# Sheet1.net
KiCad netlist of a schematic drawn in Altium Designer
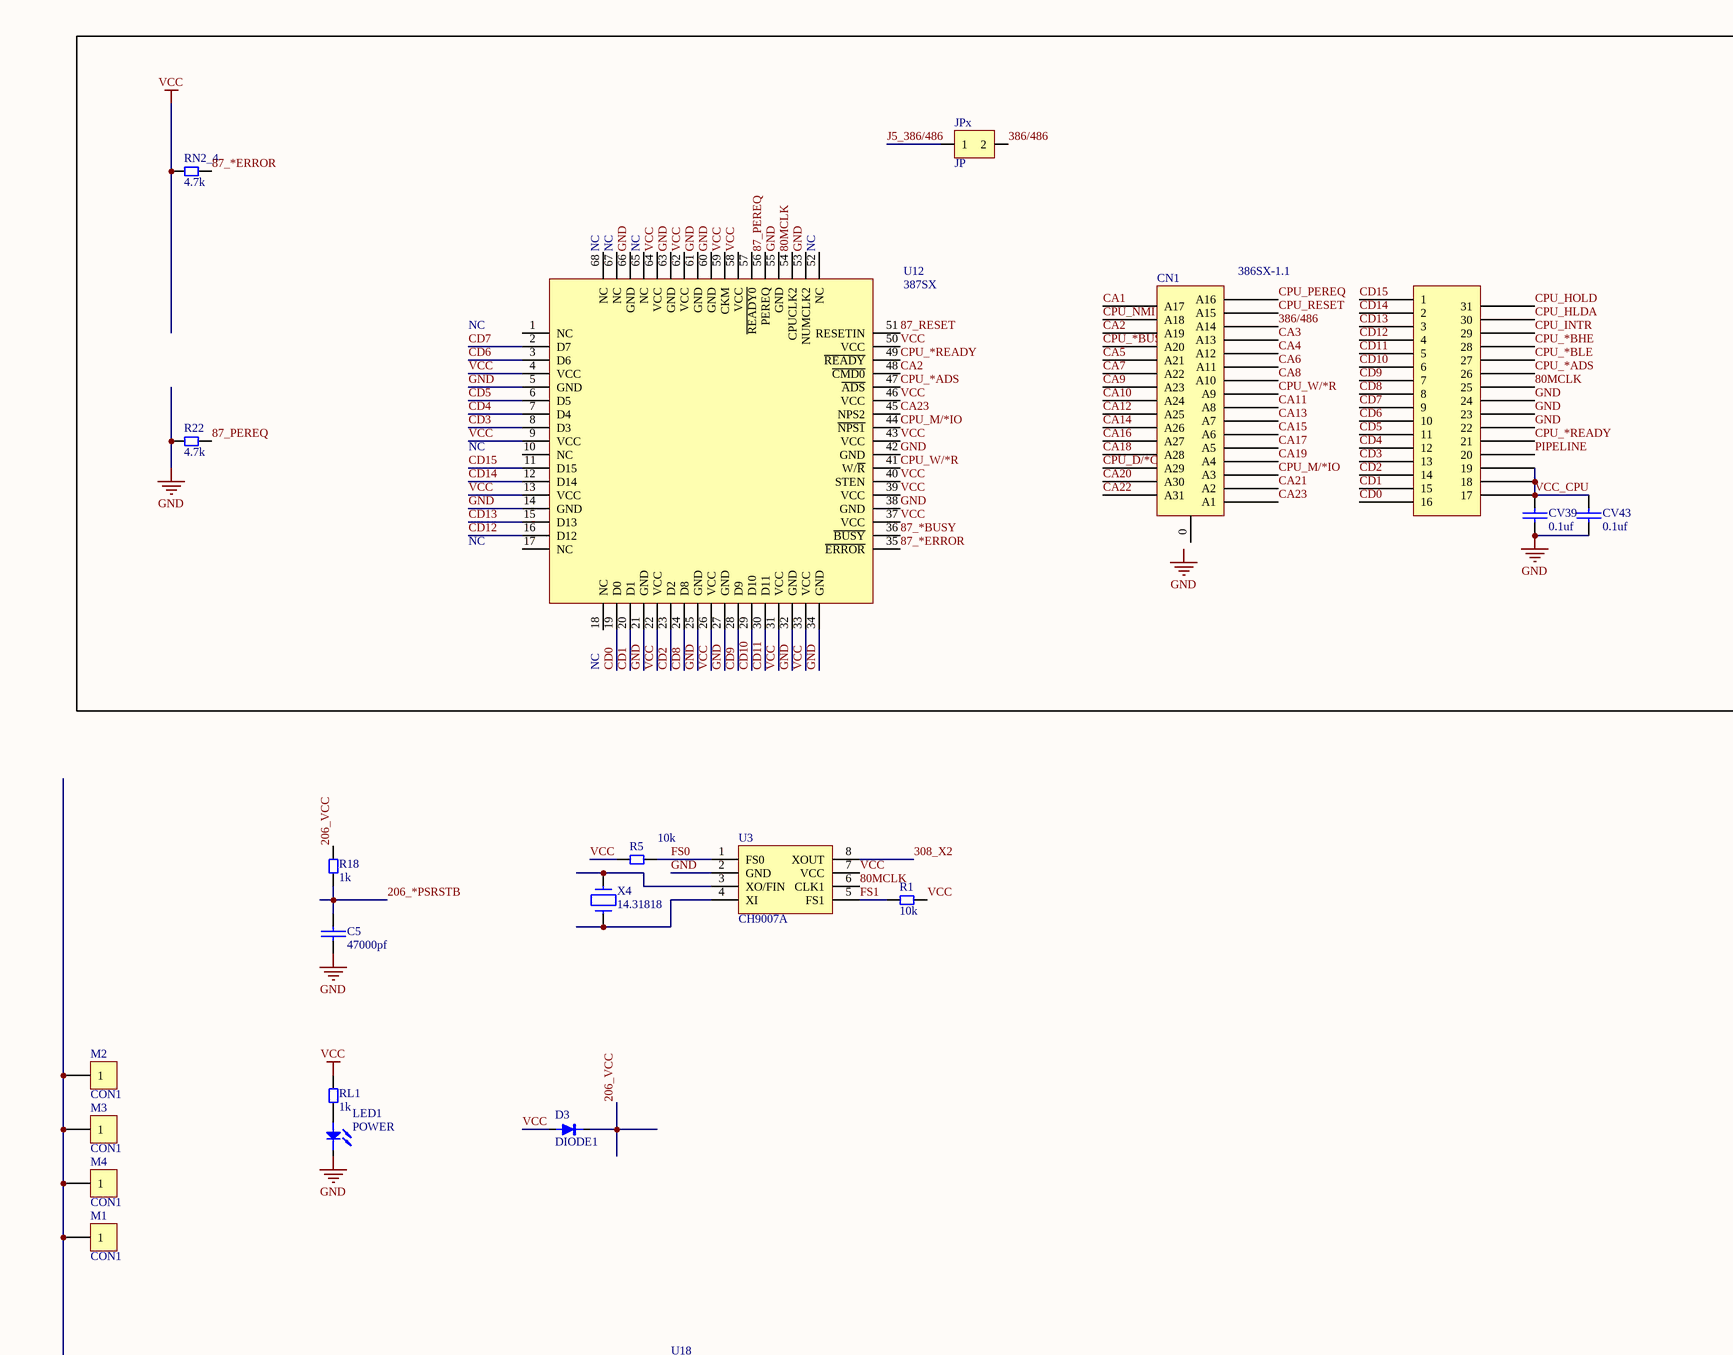
[diagram p0: Sheet1.SchDoc, top left]
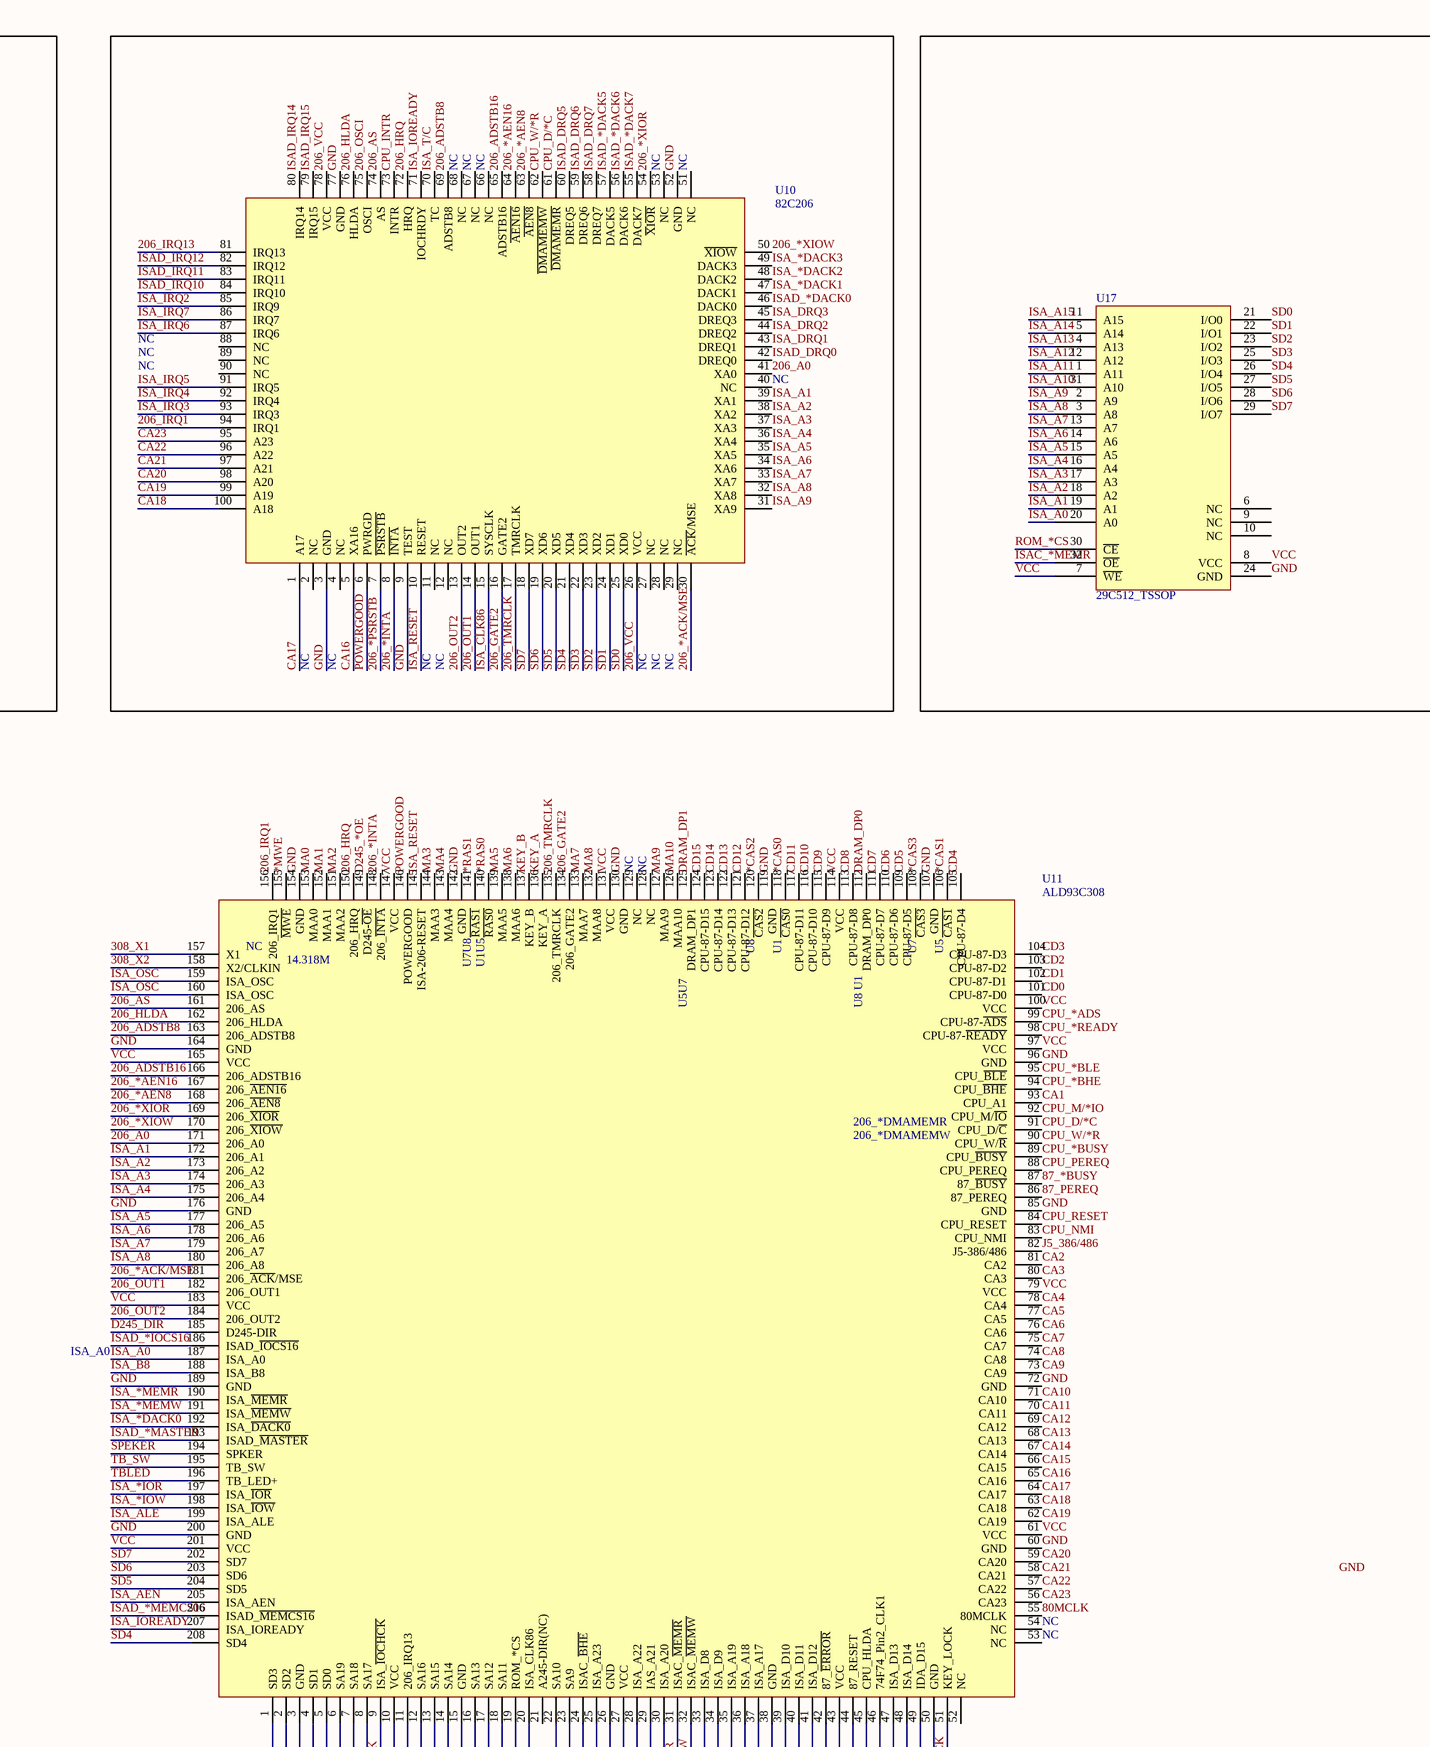
[diagram p1: Sheet1.SchDoc, top middle]
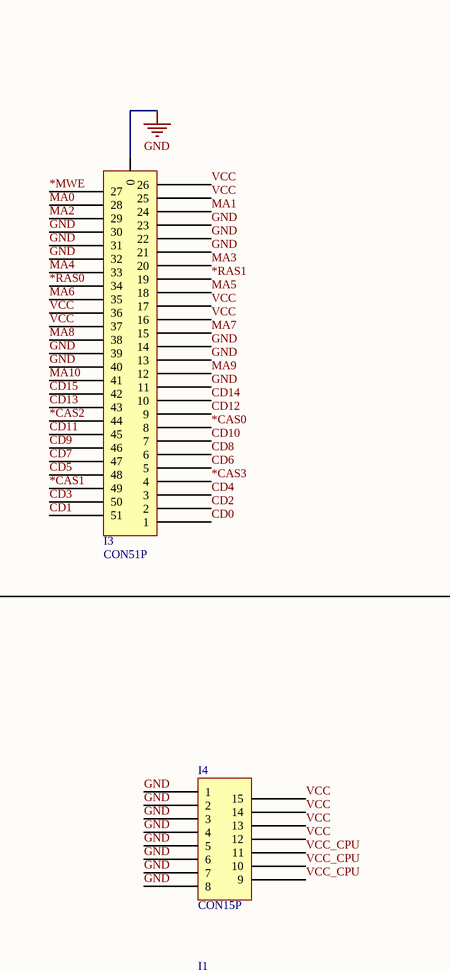
[diagram p2: Sheet1.SchDoc, top right]
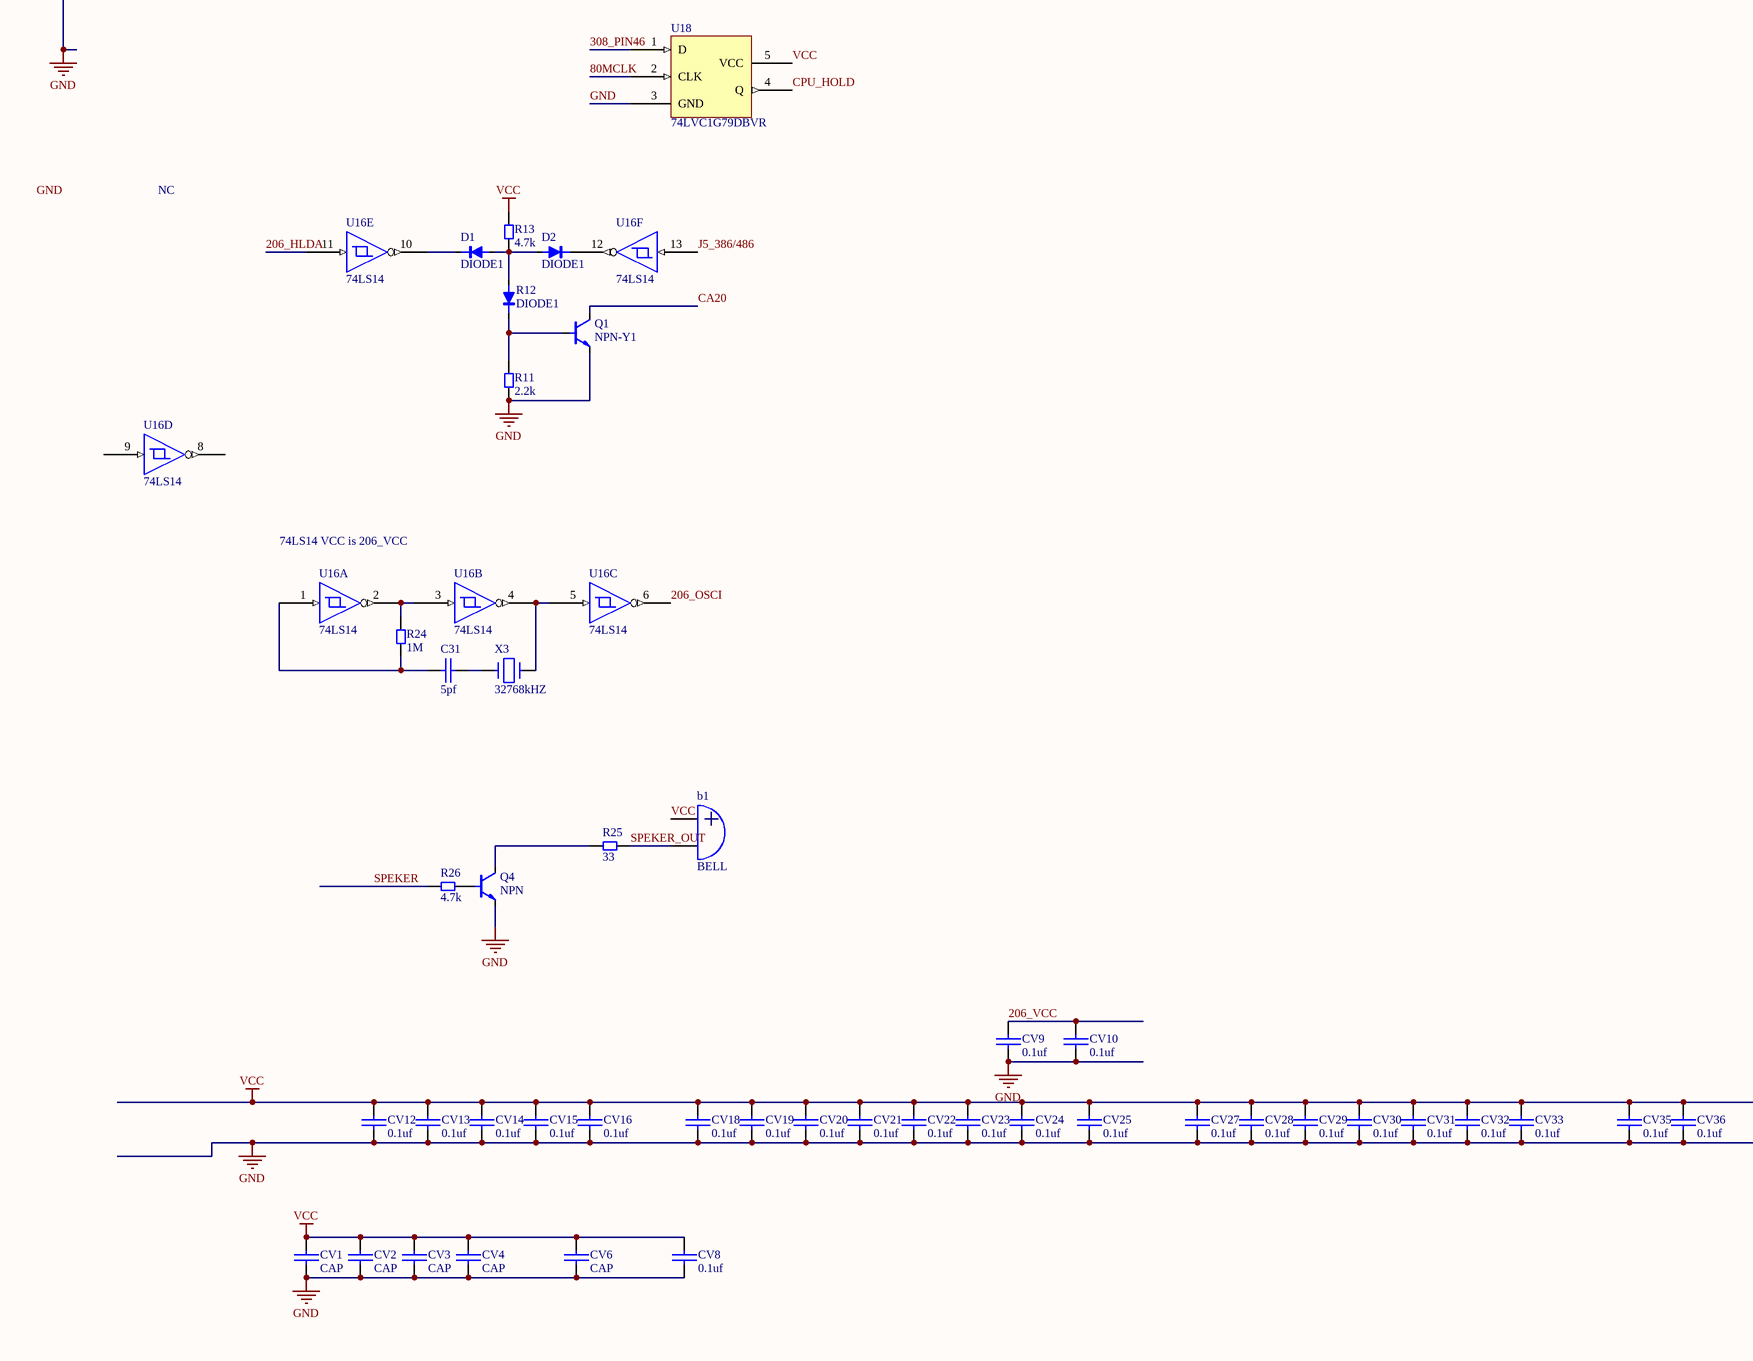
[diagram p3: Sheet1.SchDoc, bottom left]
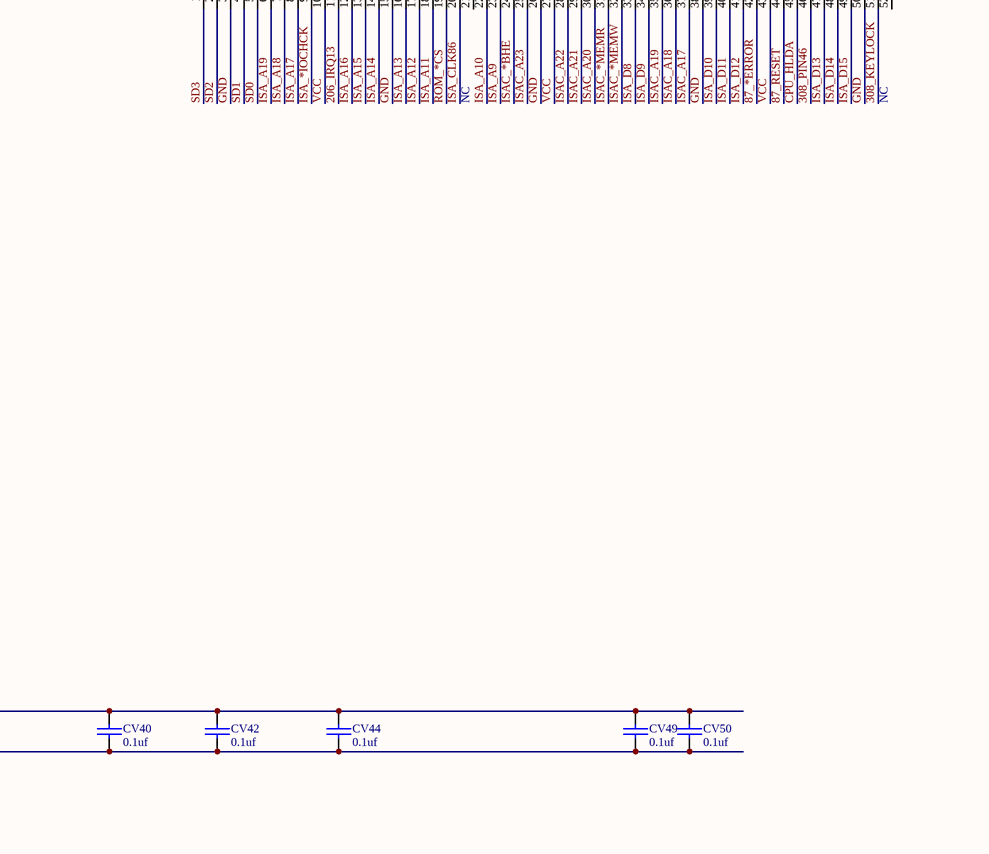
[diagram p4: Sheet1.SchDoc, bottom middle]
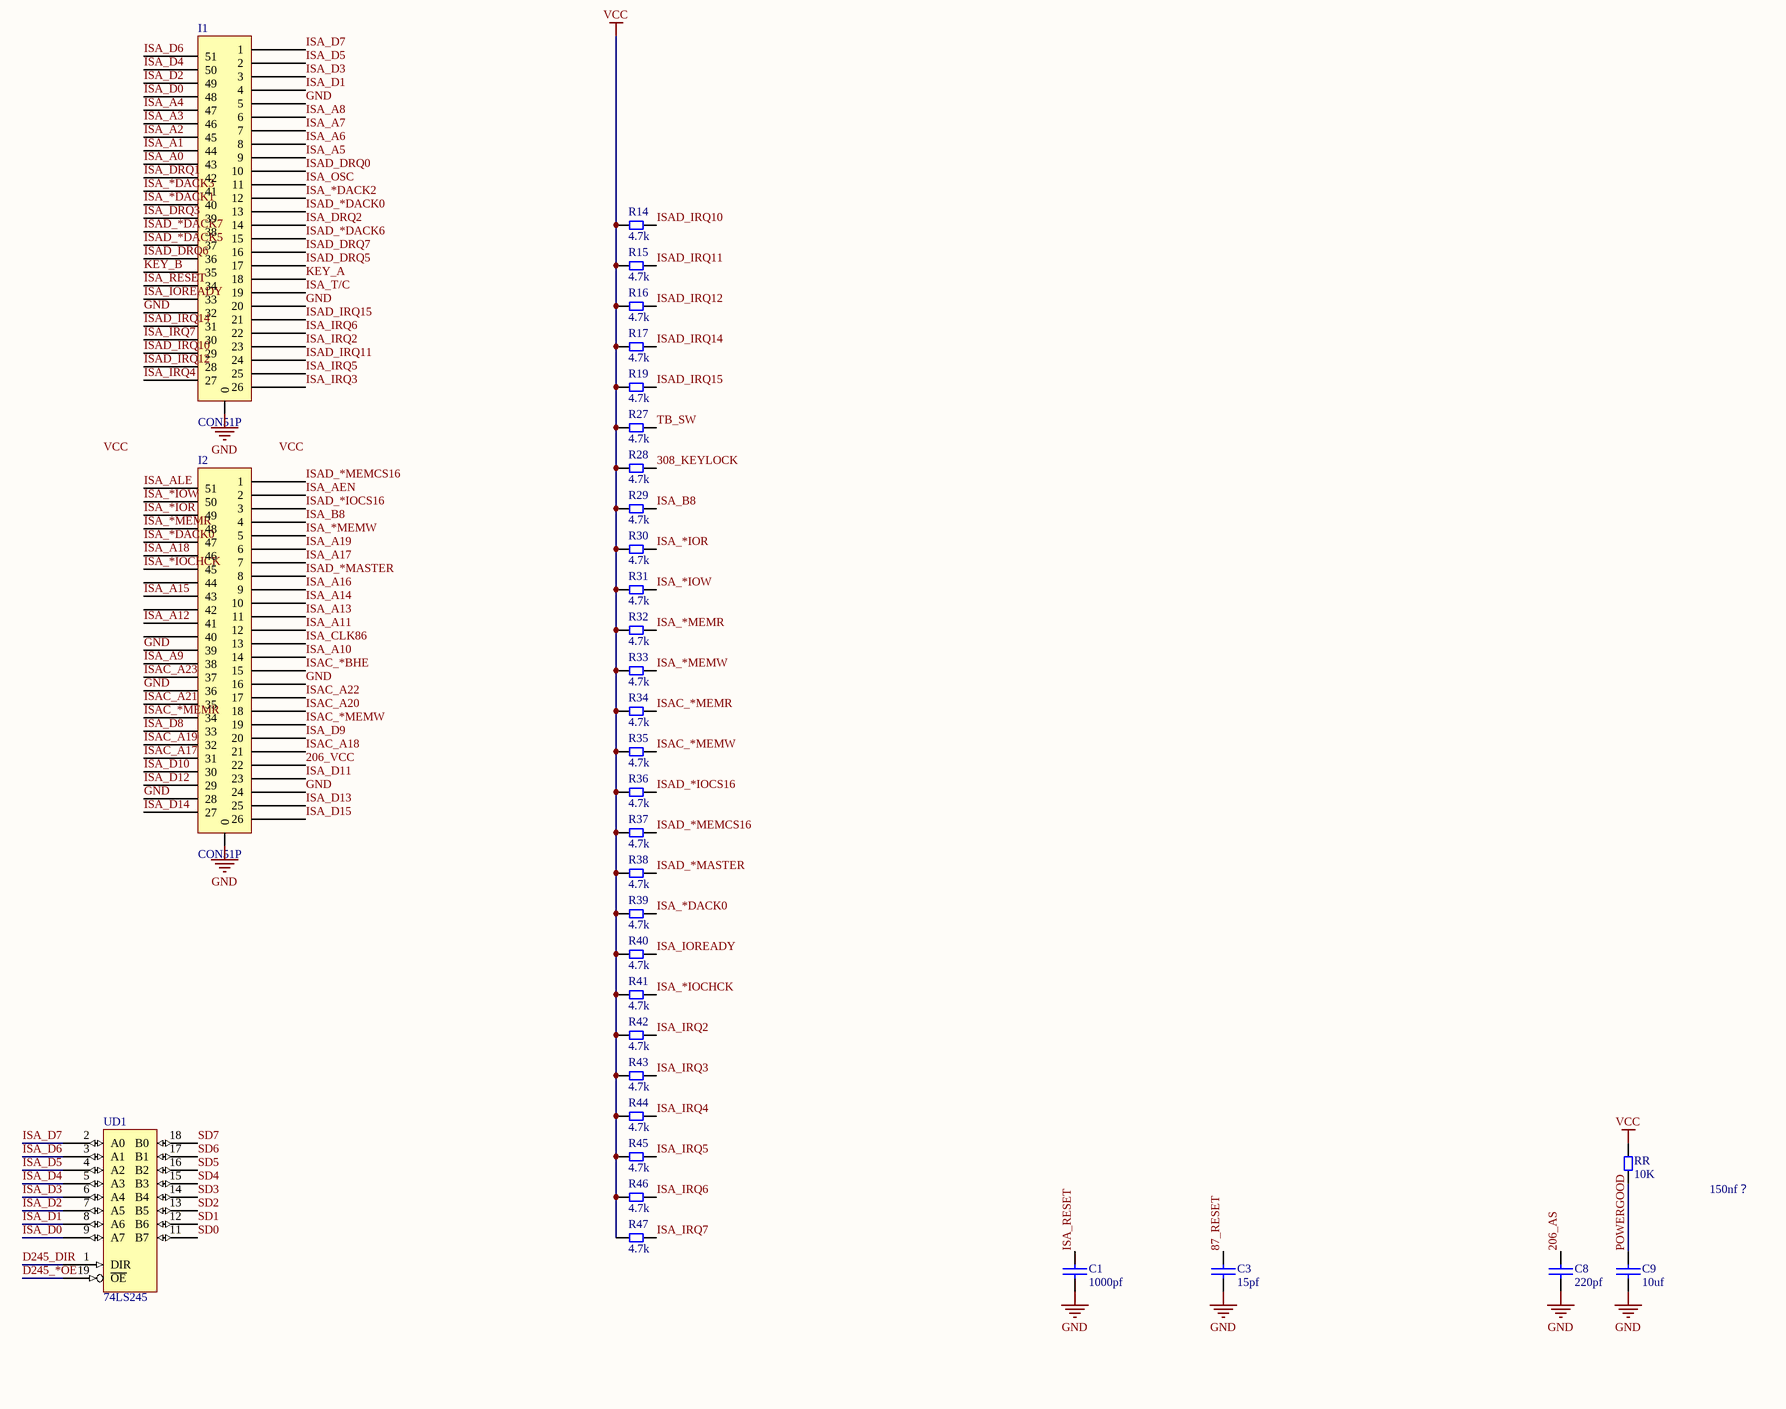
[diagram p5: Sheet1.SchDoc, bottom right]

(export (version "E")
  (design (tool "Eeschema 10.0.6"))
  (components
    (comp (ref "b1") (value "BELL") (footprint "BELL_8530") (libsource (lib "常用元件库") (part "BELL")))
    (comp (ref "C1") (value "1000pf") (footprint "C0603") (libsource (lib "电阻电容二极管") (part "CAP")))
    (comp (ref "C3") (value "15pf") (footprint "C0603") (libsource (lib "电阻电容二极管") (part "CAP")))
    (comp (ref "C5") (value "47000pf") (footprint "C0603") (libsource (lib "电阻电容二极管") (part "CAP")))
    (comp (ref "C8") (value "220pf") (footprint "C0603") (libsource (lib "电阻电容二极管") (part "CAP")))
    (comp (ref "C9") (value "10uf") (footprint "C0603") (libsource (lib "电阻电容二极管") (part "CAP")))
    (comp (ref "C31") (value "5pf") (footprint "C0603") (libsource (lib "电阻电容二极管") (part "CAP")))
    (comp (ref "CN1") (value "386SX-1.1") (footprint "MY-386SX1") (libsource (lib "微机原理") (part "386SX-1.1")))
    (comp (ref "CV1") (value "CAP") (footprint "C0805") (libsource (lib "电阻电容二极管") (part "CAP")))
    (comp (ref "CV2") (value "CAP") (footprint "C0805") (libsource (lib "电阻电容二极管") (part "CAP")))
    (comp (ref "CV3") (value "CAP") (footprint "C0805") (libsource (lib "电阻电容二极管") (part "CAP")))
    (comp (ref "CV4") (value "CAP") (footprint "C0805") (libsource (lib "电阻电容二极管") (part "CAP")))
    (comp (ref "CV6") (value "CAP") (footprint "C0805") (libsource (lib "电阻电容二极管") (part "CAP")))
    (comp (ref "CV8") (value "0.1uf") (footprint "C0603") (libsource (lib "电阻电容二极管") (part "CAP")))
    (comp (ref "CV9") (value "0.1uf") (footprint "C0603") (libsource (lib "电阻电容二极管") (part "CAP")))
    (comp (ref "CV10") (value "0.1uf") (footprint "C0603") (libsource (lib "电阻电容二极管") (part "CAP")))
    (comp (ref "CV12") (value "0.1uf") (footprint "C0603") (libsource (lib "电阻电容二极管") (part "CAP")))
    (comp (ref "CV13") (value "0.1uf") (footprint "C0603") (libsource (lib "电阻电容二极管") (part "CAP")))
    (comp (ref "CV14") (value "0.1uf") (footprint "C0603") (libsource (lib "电阻电容二极管") (part "CAP")))
    (comp (ref "CV15") (value "0.1uf") (footprint "C0603") (libsource (lib "电阻电容二极管") (part "CAP")))
    (comp (ref "CV16") (value "0.1uf") (footprint "C0603") (libsource (lib "电阻电容二极管") (part "CAP")))
    (comp (ref "CV18") (value "0.1uf") (footprint "C0603") (libsource (lib "电阻电容二极管") (part "CAP")))
    (comp (ref "CV19") (value "0.1uf") (footprint "C0603") (libsource (lib "电阻电容二极管") (part "CAP")))
    (comp (ref "CV20") (value "0.1uf") (footprint "C0603") (libsource (lib "电阻电容二极管") (part "CAP")))
    (comp (ref "CV21") (value "0.1uf") (footprint "C0603") (libsource (lib "电阻电容二极管") (part "CAP")))
    (comp (ref "CV22") (value "0.1uf") (footprint "C0603") (libsource (lib "电阻电容二极管") (part "CAP")))
    (comp (ref "CV23") (value "0.1uf") (footprint "C0603") (libsource (lib "电阻电容二极管") (part "CAP")))
    (comp (ref "CV24") (value "0.1uf") (footprint "C0603") (libsource (lib "电阻电容二极管") (part "CAP")))
    (comp (ref "CV25") (value "0.1uf") (footprint "C0603") (libsource (lib "电阻电容二极管") (part "CAP")))
    (comp (ref "CV27") (value "0.1uf") (footprint "C0603") (libsource (lib "电阻电容二极管") (part "CAP")))
    (comp (ref "CV28") (value "0.1uf") (footprint "C0603") (libsource (lib "电阻电容二极管") (part "CAP")))
    (comp (ref "CV29") (value "0.1uf") (footprint "C0603") (libsource (lib "电阻电容二极管") (part "CAP")))
    (comp (ref "CV30") (value "0.1uf") (footprint "C0603") (libsource (lib "电阻电容二极管") (part "CAP")))
    (comp (ref "CV31") (value "0.1uf") (footprint "C0603") (libsource (lib "电阻电容二极管") (part "CAP")))
    (comp (ref "CV32") (value "0.1uf") (footprint "C0603") (libsource (lib "电阻电容二极管") (part "CAP")))
    (comp (ref "CV33") (value "0.1uf") (footprint "C0603") (libsource (lib "电阻电容二极管") (part "CAP")))
    (comp (ref "CV35") (value "0.1uf") (footprint "C0603") (libsource (lib "电阻电容二极管") (part "CAP")))
    (comp (ref "CV36") (value "0.1uf") (footprint "C0603") (libsource (lib "电阻电容二极管") (part "CAP")))
    (comp (ref "CV39") (value "0.1uf") (footprint "C0603") (libsource (lib "电阻电容二极管") (part "CAP")))
    (comp (ref "CV40") (value "0.1uf") (footprint "C0603") (libsource (lib "电阻电容二极管") (part "CAP")))
    (comp (ref "CV42") (value "0.1uf") (footprint "C0603") (libsource (lib "电阻电容二极管") (part "CAP")))
    (comp (ref "CV43") (value "0.1uf") (footprint "C0603") (libsource (lib "电阻电容二极管") (part "CAP")))
    (comp (ref "CV44") (value "0.1uf") (footprint "C0603") (libsource (lib "电阻电容二极管") (part "CAP")))
    (comp (ref "CV49") (value "0.1uf") (footprint "C0603") (libsource (lib "电阻电容二极管") (part "CAP")))
    (comp (ref "CV50") (value "0.1uf") (footprint "C0603") (libsource (lib "电阻电容二极管") (part "CAP")))
    (comp (ref "D1") (value "DIODE1") (footprint "SOD323") (libsource (lib "电阻电容二极管") (part "DIODE1")))
    (comp (ref "D2") (value "DIODE1") (footprint "SOD323") (libsource (lib "电阻电容二极管") (part "DIODE1")))
    (comp (ref "D3") (value "DIODE1") (footprint "SMx") (libsource (lib "常用元件库") (part "DIODE1")))
    (comp (ref "I1") (value "CON51P") (footprint "BTB1.0-51P-b") (libsource (lib "常用元件库") (part "CON51P")))
    (comp (ref "I2") (value "CON51P") (footprint "BTB1.0-51P-b") (libsource (lib "常用元件库") (part "CON51P")))
    (comp (ref "I3") (value "CON51P") (footprint "BTB1.0-51P-b") (libsource (lib "") (part "CON51P_1")))
    (comp (ref "I4") (value "CON15P") (footprint "BTB1.0-15P-B") (libsource (lib "常用元件库") (part "CON15P")))
    (comp (ref "JPx") (value "JP") (footprint "SIP2(2.0)") (libsource (lib "常用元件库") (part "JP-2")))
    (comp (ref "LED1") (value "POWER") (footprint "LED0603") (libsource (lib "电阻电容二极管") (part "LED")))
    (comp (ref "M1") (value "CON1") (footprint "M2A") (libsource (lib "常用元件库") (part "CON1")))
    (comp (ref "M2") (value "CON1") (footprint "MY-M2") (libsource (lib "常用元件库") (part "CON1")))
    (comp (ref "M3") (value "CON1") (footprint "MY-M2") (libsource (lib "常用元件库") (part "CON1")))
    (comp (ref "M4") (value "CON1") (footprint "M2A") (libsource (lib "常用元件库") (part "CON1")))
    (comp (ref "Q1") (value "NPN-Y1") (footprint "SOT23") (libsource (lib "电阻电容二极管") (part "NPN")))
    (comp (ref "Q4") (value "NPN") (footprint "SOT23") (libsource (lib "电阻电容二极管") (part "NPN")))
    (comp (ref "R1") (value "10k") (footprint "R0603") (libsource (lib "电阻电容二极管") (part "RES2")))
    (comp (ref "R5") (value "10k") (footprint "R0603") (libsource (lib "电阻电容二极管") (part "RES2")))
    (comp (ref "R11") (value "2.2k") (footprint "R0603") (libsource (lib "电阻电容二极管") (part "RES2")))
    (comp (ref "R12") (value "DIODE1") (footprint "SOD323") (libsource (lib "电阻电容二极管") (part "DIODE1")))
    (comp (ref "R13") (value "4.7k") (footprint "R0603") (libsource (lib "电阻电容二极管") (part "RES2")))
    (comp (ref "R14") (value "4.7k") (footprint "R0603") (libsource (lib "电阻电容二极管") (part "RES2")))
    (comp (ref "R15") (value "4.7k") (footprint "R0603") (libsource (lib "电阻电容二极管") (part "RES2")))
    (comp (ref "R16") (value "4.7k") (footprint "R0603") (libsource (lib "电阻电容二极管") (part "RES2")))
    (comp (ref "R17") (value "4.7k") (footprint "R0603") (libsource (lib "电阻电容二极管") (part "RES2")))
    (comp (ref "R18") (value "1k") (footprint "R0603") (libsource (lib "电阻电容二极管") (part "RES2")))
    (comp (ref "R19") (value "4.7k") (footprint "R0603") (libsource (lib "电阻电容二极管") (part "RES2")))
    (comp (ref "R22") (value "4.7k") (footprint "R0603") (libsource (lib "电阻电容二极管") (part "RES2")))
    (comp (ref "R24") (value "1M") (footprint "R0603") (libsource (lib "电阻电容二极管") (part "RES2")))
    (comp (ref "R25") (value "33") (footprint "R0603") (libsource (lib "电阻电容二极管") (part "RES2")))
    (comp (ref "R26") (value "4.7k") (footprint "R0603") (libsource (lib "电阻电容二极管") (part "RES2")))
    (comp (ref "R27") (value "4.7k") (footprint "R0603") (libsource (lib "电阻电容二极管") (part "RES2")))
    (comp (ref "R28") (value "4.7k") (footprint "R0603") (libsource (lib "电阻电容二极管") (part "RES2")))
    (comp (ref "R29") (value "4.7k") (footprint "R0603") (libsource (lib "电阻电容二极管") (part "RES2")))
    (comp (ref "R30") (value "4.7k") (footprint "R0603") (libsource (lib "电阻电容二极管") (part "RES2")))
    (comp (ref "R31") (value "4.7k") (footprint "R0603") (libsource (lib "电阻电容二极管") (part "RES2")))
    (comp (ref "R32") (value "4.7k") (footprint "R0603") (libsource (lib "电阻电容二极管") (part "RES2")))
    (comp (ref "R33") (value "4.7k") (footprint "R0603") (libsource (lib "电阻电容二极管") (part "RES2")))
    (comp (ref "R34") (value "4.7k") (footprint "R0603") (libsource (lib "电阻电容二极管") (part "RES2")))
    (comp (ref "R35") (value "4.7k") (footprint "R0603") (libsource (lib "电阻电容二极管") (part "RES2")))
    (comp (ref "R36") (value "4.7k") (footprint "R0603") (libsource (lib "电阻电容二极管") (part "RES2")))
    (comp (ref "R37") (value "4.7k") (footprint "R0603") (libsource (lib "电阻电容二极管") (part "RES2")))
    (comp (ref "R38") (value "4.7k") (footprint "R0603") (libsource (lib "电阻电容二极管") (part "RES2")))
    (comp (ref "R39") (value "4.7k") (footprint "R0603") (libsource (lib "电阻电容二极管") (part "RES2")))
    (comp (ref "R40") (value "4.7k") (footprint "R0603") (libsource (lib "电阻电容二极管") (part "RES2")))
    (comp (ref "R41") (value "4.7k") (footprint "R0603") (libsource (lib "电阻电容二极管") (part "RES2")))
    (comp (ref "R42") (value "4.7k") (footprint "R0603") (libsource (lib "电阻电容二极管") (part "RES2")))
    (comp (ref "R43") (value "4.7k") (footprint "R0603") (libsource (lib "电阻电容二极管") (part "RES2")))
    (comp (ref "R44") (value "4.7k") (footprint "R0603") (libsource (lib "电阻电容二极管") (part "RES2")))
    (comp (ref "R45") (value "4.7k") (footprint "R0603") (libsource (lib "电阻电容二极管") (part "RES2")))
    (comp (ref "R46") (value "4.7k") (footprint "R0603") (libsource (lib "电阻电容二极管") (part "RES2")))
    (comp (ref "R47") (value "4.7k") (footprint "R0603") (libsource (lib "电阻电容二极管") (part "RES2")))
    (comp (ref "RL1") (value "1k") (footprint "R0603") (libsource (lib "电阻电容二极管") (part "RES2")))
    (comp (ref "RN2_4") (value "4.7k") (footprint "R0603") (libsource (lib "电阻电容二极管") (part "RES2")))
    (comp (ref "RR") (value "10K") (footprint "R0603") (libsource (lib "电阻电容二极管") (part "RES2")))
    (comp (ref "U3") (value "CH9007A") (footprint "DIP8 - SOJ") (libsource (lib "微机原理") (part "CH9007A")))
    (comp (ref "U10") (value "82C206") (footprint "PQFP100B") (libsource (lib "微机原理") (part "82C206")))
    (comp (ref "U11") (value "ALD93C308") (libsource (lib "微机原理") (part "ALD93C308")))
    (comp (ref "U12") (value "387SX") (footprint "PLCC68") (libsource (lib "微机原理") (part "387SX")))
    (comp (ref "U16") (value "74LS14") (footprint "SO-14") (libsource (lib "TTL74系列IC") (part "74LS14")))
    (comp (ref "U17")
      (value "29C512_TSSOP")
      (footprint "TSSOP32")
      (libsource (lib "微机原理") (part "29C512_TSSOP"))
    )
    (comp (ref "U18")
      (value "74LVC1G79DBVR")
      (footprint "SOT23-5")
      (libsource (lib "微机原理") (part "74LVC1G79DBVR"))
    )
    (comp (ref "UD1") (value "74LS245") (footprint "TSSOP-20") (libsource (lib "微机原理") (part "74LS245")))
    (comp (ref "X3") (value "32768kHZ") (footprint "CRY3215A") (libsource (lib "常用元件库") (part "CRYSTAL")))
    (comp (ref "X4") (value "14.31818") (footprint "5032") (libsource (lib "常用元件库") (part "CRYSTAL")))
  )
  (nets
    (net (code "1") (name "/*CAS0") (class "Default")
      (node (ref "I3") (pin "8") (pinfunction "8_8") (pintype "passive"))
      (node (ref "U11") (pin "118") (pinfunction "~{CAS0}_118") (pintype "passive"))
    )
    (net (code "2") (name "/*CAS1") (class "Default")
      (node (ref "I3") (pin "49") (pinfunction "49_49") (pintype "passive"))
      (node (ref "U11") (pin "106") (pinfunction "~{CAS1}_106") (pintype "passive"))
    )
    (net (code "3") (name "/*CAS2") (class "Default")
      (node (ref "I3") (pin "44") (pinfunction "44_44") (pintype "passive"))
      (node (ref "U11") (pin "120") (pinfunction "~{CAS2}_120") (pintype "passive"))
    )
    (net (code "4") (name "/*CAS3") (class "Default")
      (node (ref "I3") (pin "4") (pinfunction "4_4") (pintype "passive"))
      (node (ref "U11") (pin "108") (pinfunction "~{CAS3}_108") (pintype "passive"))
    )
    (net (code "5") (name "/*MWE") (class "Default")
      (node (ref "I3") (pin "27") (pinfunction "27_27") (pintype "passive"))
      (node (ref "U11") (pin "155") (pinfunction "~{MWE}_155") (pintype "passive"))
    )
    (net (code "6") (name "/*RAS0") (class "Default")
      (node (ref "I3") (pin "34") (pinfunction "34_34") (pintype "passive"))
      (node (ref "U11") (pin "140") (pinfunction "~{RAS0}_140") (pintype "passive"))
    )
    (net (code "7") (name "/*RAS1") (class "Default")
      (node (ref "I3") (pin "19") (pinfunction "19_19") (pintype "passive"))
      (node (ref "U11") (pin "141") (pinfunction "~{RAS1}_141") (pintype "passive"))
    )
    (net (code "8") (name "/80MCLK") (class "Default")
      (node (ref "CN1") (pin "25") (pinfunction "25_25") (pintype "passive"))
      (node (ref "U11") (pin "55") (pinfunction "80MCLK_55") (pintype "passive"))
      (node (ref "U12") (pin "54") (pinfunction "CPUCLK2_54") (pintype "passive"))
      (node (ref "U18") (pin "2") (pinfunction "CLK_2") (pintype "input"))
      (node (ref "U3") (pin "6") (pinfunction "CLK1_6") (pintype "passive"))
    )
    (net (code "9") (name "/87_*BUSY") (class "Default")
      (node (ref "U11") (pin "87") (pinfunction "87_~{BUSY}_87") (pintype "passive"))
      (node (ref "U12") (pin "36") (pinfunction "~{BUSY}_36") (pintype "passive"))
    )
    (net (code "10") (name "/87_*ERROR") (class "Default")
      (node (ref "RN2_4") (pin "1") (pinfunction "1_1") (pintype "passive"))
      (node (ref "U11") (pin "42") (pinfunction "87_~{ERROR}_42") (pintype "passive"))
      (node (ref "U12") (pin "35") (pinfunction "~{ERROR}_35") (pintype "passive"))
    )
    (net (code "11") (name "/87_PEREQ") (class "Default")
      (node (ref "R22") (pin "2") (pinfunction "2_2") (pintype "passive"))
      (node (ref "U11") (pin "86") (pinfunction "87_PEREQ_86") (pintype "passive"))
      (node (ref "U12") (pin "56") (pinfunction "PEREQ_56") (pintype "passive"))
    )
    (net (code "12") (name "/87_RESET") (class "Default")
      (node (ref "C3") (pin "1") (pinfunction "1_1") (pintype "passive"))
      (node (ref "U11") (pin "44") (pinfunction "87_RESET_44") (pintype "passive"))
      (node (ref "U12") (pin "51") (pinfunction "RESETIN_51") (pintype "passive"))
    )
    (net (code "13") (name "/206_*ACK{slash}MSE") (class "Default")
      (node (ref "U10") (pin "30") (pinfunction "~{ACK}/MSE_30") (pintype "passive"))
      (node (ref "U11") (pin "181") (pinfunction "206_~{ACK}/MSE_181") (pintype "passive"))
    )
    (net (code "14") (name "/206_*AEN8") (class "Default")
      (node (ref "U10") (pin "63") (pinfunction "~{AEN8}_63") (pintype "passive"))
      (node (ref "U11") (pin "168") (pinfunction "206_~{AEN8}_168") (pintype "passive"))
    )
    (net (code "15") (name "/206_*AEN16") (class "Default")
      (node (ref "U10") (pin "64") (pinfunction "~{AEN16}_64") (pintype "passive"))
      (node (ref "U11") (pin "167") (pinfunction "206_~{AEN16}_167") (pintype "passive"))
    )
    (net (code "16") (name "/206_*INTA") (class "Default")
      (node (ref "U10") (pin "8") (pinfunction "~{INTA}_8") (pintype "passive"))
      (node (ref "U11") (pin "148") (pinfunction "206_~{INTA}_148") (pintype "passive"))
    )
    (net (code "17") (name "/206_*PSRSTB") (class "Default")
      (node (ref "C5") (pin "2") (pinfunction "2_2") (pintype "passive"))
      (node (ref "R18") (pin "1") (pinfunction "1_1") (pintype "passive"))
      (node (ref "U10") (pin "7") (pinfunction "~{PSRSTB}_7") (pintype "passive"))
    )
    (net (code "18") (name "/206_*XIOR") (class "Default")
      (node (ref "U10") (pin "54") (pinfunction "~{X}I~{OR}_54") (pintype "passive"))
      (node (ref "U11") (pin "169") (pinfunction "206_~{XIOR}_169") (pintype "passive"))
    )
    (net (code "19") (name "/206_*XIOW") (class "Default")
      (node (ref "U10") (pin "50") (pinfunction "~{XIOW}_50") (pintype "passive"))
      (node (ref "U11") (pin "170") (pinfunction "206_~{XIOW}_170") (pintype "passive"))
    )
    (net (code "20") (name "/206_A0") (class "Default")
      (node (ref "U10") (pin "41") (pinfunction "XA0_41") (pintype "passive"))
      (node (ref "U11") (pin "171") (pinfunction "206_A0_171") (pintype "passive"))
    )
    (net (code "21") (name "/206_ADSTB8") (class "Default")
      (node (ref "U10") (pin "69") (pinfunction "ADSTB8_69") (pintype "passive"))
      (node (ref "U11") (pin "163") (pinfunction "206_ADSTB8_163") (pintype "passive"))
    )
    (net (code "22") (name "/206_ADSTB16") (class "Default")
      (node (ref "U10") (pin "65") (pinfunction "ADSTB16_65") (pintype "passive"))
      (node (ref "U11") (pin "166") (pinfunction "206_ADSTB16_166") (pintype "passive"))
    )
    (net (code "23") (name "/206_AS") (class "Default")
      (node (ref "C8") (pin "1") (pinfunction "1_1") (pintype "passive"))
      (node (ref "U10") (pin "74") (pinfunction "AS_74") (pintype "passive"))
      (node (ref "U11") (pin "161") (pinfunction "206_AS_161") (pintype "passive"))
    )
    (net (code "24") (name "/206_GATE2") (class "Default")
      (node (ref "U10") (pin "16") (pinfunction "GATE2_16") (pintype "passive"))
      (node (ref "U11") (pin "134") (pinfunction "206_GATE2_134") (pintype "passive"))
    )
    (net (code "25") (name "/206_HLDA") (class "Default")
      (node (ref "U10") (pin "76") (pinfunction "HLDA_76") (pintype "passive"))
      (node (ref "U11") (pin "162") (pinfunction "206_HLDA_162") (pintype "passive"))
      (node (ref "U16") (pin "11") (pintype "input"))
    )
    (net (code "26") (name "/206_HRQ") (class "Default")
      (node (ref "U10") (pin "72") (pinfunction "HRQ_72") (pintype "passive"))
      (node (ref "U11") (pin "150") (pinfunction "206_HRQ_150") (pintype "passive"))
    )
    (net (code "27") (name "/206_IRQ1") (class "Default")
      (node (ref "U10") (pin "94") (pinfunction "IRQ1_94") (pintype "passive"))
      (node (ref "U11") (pin "156") (pinfunction "206_IRQ1_156") (pintype "passive"))
    )
    (net (code "28") (name "/206_IRQ13") (class "Default")
      (node (ref "U10") (pin "81") (pinfunction "IRQ13_81") (pintype "passive"))
      (node (ref "U11") (pin "11") (pinfunction "206_IRQ13_11") (pintype "passive"))
    )
    (net (code "29") (name "/206_OSCI") (class "Default")
      (node (ref "U10") (pin "75") (pinfunction "OSCI_75") (pintype "passive"))
      (node (ref "U16") (pin "6") (pintype "output"))
    )
    (net (code "30") (name "/206_OUT1") (class "Default")
      (node (ref "U10") (pin "14") (pinfunction "OUT1_14") (pintype "passive"))
      (node (ref "U11") (pin "182") (pinfunction "206_OUT1_182") (pintype "passive"))
    )
    (net (code "31") (name "/206_OUT2") (class "Default")
      (node (ref "U10") (pin "13") (pinfunction "OUT2_13") (pintype "passive"))
      (node (ref "U11") (pin "184") (pinfunction "206_OUT2_184") (pintype "passive"))
    )
    (net (code "32") (name "/206_TMRCLK") (class "Default")
      (node (ref "U10") (pin "17") (pinfunction "TMRCLK_17") (pintype "passive"))
      (node (ref "U11") (pin "135") (pinfunction "206_TMRCLK_135") (pintype "passive"))
    )
    (net (code "33") (name "/206_VCC") (class "Default")
      (node (ref "CV10") (pin "1") (pinfunction "1_1") (pintype "passive"))
      (node (ref "CV9") (pin "1") (pinfunction "1_1") (pintype "passive"))
      (node (ref "D3") (pin "K") (pinfunction "K_K") (pintype "passive"))
      (node (ref "I2") (pin "22") (pinfunction "22_22") (pintype "passive"))
      (node (ref "R18") (pin "2") (pinfunction "2_2") (pintype "passive"))
      (node (ref "U10") (pin "26") (pinfunction "VCC_26") (pintype "passive"))
      (node (ref "U10") (pin "78") (pinfunction "VCC_78") (pintype "passive"))
    )
    (net (code "34") (name "/308_KEYLOCK") (class "Default")
      (node (ref "R28") (pin "2") (pinfunction "2_2") (pintype "passive"))
      (node (ref "U11") (pin "51") (pinfunction "KEY_LOCK_51") (pintype "passive"))
    )
    (net (code "35") (name "/308_PIN46") (class "Default")
      (node (ref "U11") (pin "46") (pinfunction "74F74_Pin2_CLK1_46") (pintype "passive"))
      (node (ref "U18") (pin "1") (pinfunction "D_1") (pintype "input"))
    )
    (net (code "36") (name "/308_X1") (class "Default")
      (node (ref "U11") (pin "157") (pinfunction "X1_157") (pintype "passive"))
    )
    (net (code "37") (name "/308_X2") (class "Default")
      (node (ref "U11") (pin "158") (pinfunction "X2/CLKIN_158") (pintype "passive"))
      (node (ref "U3") (pin "8") (pinfunction "XOUT_8") (pintype "passive"))
    )
    (net (code "38") (name "/386{slash}486") (class "Default")
      (node (ref "CN1") (pin "A14") (pinfunction "A14_A14") (pintype "passive"))
      (node (ref "JPx") (pin "2") (pinfunction "2_2") (pintype "passive"))
    )
    (net (code "39") (name "/CA1") (class "Default")
      (node (ref "CN1") (pin "A17") (pinfunction "A17_A17") (pintype "passive"))
      (node (ref "U11") (pin "93") (pinfunction "CPU_A1_93") (pintype "passive"))
    )
    (net (code "40") (name "/CA2") (class "Default")
      (node (ref "CN1") (pin "A19") (pinfunction "A19_A19") (pintype "passive"))
      (node (ref "U11") (pin "81") (pinfunction "CA2_81") (pintype "passive"))
      (node (ref "U12") (pin "48") (pinfunction "~{CMD0}_48") (pintype "passive"))
    )
    (net (code "41") (name "/CA3") (class "Default")
      (node (ref "CN1") (pin "A13") (pinfunction "A13_A13") (pintype "passive"))
      (node (ref "U11") (pin "80") (pinfunction "CA3_80") (pintype "passive"))
    )
    (net (code "42") (name "/CA4") (class "Default")
      (node (ref "CN1") (pin "A12") (pinfunction "A12_A12") (pintype "passive"))
      (node (ref "U11") (pin "78") (pinfunction "CA4_78") (pintype "passive"))
    )
    (net (code "43") (name "/CA5") (class "Default")
      (node (ref "CN1") (pin "A21") (pinfunction "A21_A21") (pintype "passive"))
      (node (ref "U11") (pin "77") (pinfunction "CA5_77") (pintype "passive"))
    )
    (net (code "44") (name "/CA6") (class "Default")
      (node (ref "CN1") (pin "A11") (pinfunction "A11_A11") (pintype "passive"))
      (node (ref "U11") (pin "76") (pinfunction "CA6_76") (pintype "passive"))
    )
    (net (code "45") (name "/CA7") (class "Default")
      (node (ref "CN1") (pin "A22") (pinfunction "A22_A22") (pintype "passive"))
      (node (ref "U11") (pin "75") (pinfunction "CA7_75") (pintype "passive"))
    )
    (net (code "46") (name "/CA8") (class "Default")
      (node (ref "CN1") (pin "A10") (pinfunction "A10_A10") (pintype "passive"))
      (node (ref "U11") (pin "74") (pinfunction "CA8_74") (pintype "passive"))
    )
    (net (code "47") (name "/CA9") (class "Default")
      (node (ref "CN1") (pin "A23") (pinfunction "A23_A23") (pintype "passive"))
      (node (ref "U11") (pin "73") (pinfunction "CA9_73") (pintype "passive"))
    )
    (net (code "48") (name "/CA10") (class "Default")
      (node (ref "CN1") (pin "A24") (pinfunction "A24_A24") (pintype "passive"))
      (node (ref "U11") (pin "71") (pinfunction "CA10_71") (pintype "passive"))
    )
    (net (code "49") (name "/CA11") (class "Default")
      (node (ref "CN1") (pin "A8") (pinfunction "A8_A8") (pintype "passive"))
      (node (ref "U11") (pin "70") (pinfunction "CA11_70") (pintype "passive"))
    )
    (net (code "50") (name "/CA12") (class "Default")
      (node (ref "CN1") (pin "A25") (pinfunction "A25_A25") (pintype "passive"))
      (node (ref "U11") (pin "69") (pinfunction "CA12_69") (pintype "passive"))
    )
    (net (code "51") (name "/CA13") (class "Default")
      (node (ref "CN1") (pin "A7") (pinfunction "A7_A7") (pintype "passive"))
      (node (ref "U11") (pin "68") (pinfunction "CA13_68") (pintype "passive"))
    )
    (net (code "52") (name "/CA14") (class "Default")
      (node (ref "CN1") (pin "A26") (pinfunction "A26_A26") (pintype "passive"))
      (node (ref "U11") (pin "67") (pinfunction "CA14_67") (pintype "passive"))
    )
    (net (code "53") (name "/CA15") (class "Default")
      (node (ref "CN1") (pin "A6") (pinfunction "A6_A6") (pintype "passive"))
      (node (ref "U11") (pin "66") (pinfunction "CA15_66") (pintype "passive"))
    )
    (net (code "54") (name "/CA16") (class "Default")
      (node (ref "CN1") (pin "A27") (pinfunction "A27_A27") (pintype "passive"))
      (node (ref "U10") (pin "5") (pinfunction "XA16_5") (pintype "passive"))
      (node (ref "U11") (pin "65") (pinfunction "CA16_65") (pintype "passive"))
    )
    (net (code "55") (name "/CA17") (class "Default")
      (node (ref "CN1") (pin "A5") (pinfunction "A5_A5") (pintype "passive"))
      (node (ref "U10") (pin "1") (pinfunction "A17_1") (pintype "passive"))
      (node (ref "U11") (pin "64") (pinfunction "CA17_64") (pintype "passive"))
    )
    (net (code "56") (name "/CA18") (class "Default")
      (node (ref "CN1") (pin "A28") (pinfunction "A28_A28") (pintype "passive"))
      (node (ref "U10") (pin "100") (pinfunction "A18_100") (pintype "passive"))
      (node (ref "U11") (pin "63") (pinfunction "CA18_63") (pintype "passive"))
    )
    (net (code "57") (name "/CA19") (class "Default")
      (node (ref "CN1") (pin "A4") (pinfunction "A4_A4") (pintype "passive"))
      (node (ref "U10") (pin "99") (pinfunction "A19_99") (pintype "passive"))
      (node (ref "U11") (pin "62") (pinfunction "CA19_62") (pintype "passive"))
    )
    (net (code "58") (name "/CA20") (class "Default")
      (node (ref "CN1") (pin "A30") (pinfunction "A30_A30") (pintype "passive"))
      (node (ref "Q1") (pin "C") (pinfunction "c_C") (pintype "passive"))
      (node (ref "U10") (pin "98") (pinfunction "A20_98") (pintype "passive"))
      (node (ref "U11") (pin "59") (pinfunction "CA20_59") (pintype "passive"))
    )
    (net (code "59") (name "/CA21") (class "Default")
      (node (ref "CN1") (pin "A2") (pinfunction "A2_A2") (pintype "passive"))
      (node (ref "U10") (pin "97") (pinfunction "A21_97") (pintype "passive"))
      (node (ref "U11") (pin "58") (pinfunction "CA21_58") (pintype "passive"))
    )
    (net (code "60") (name "/CA22") (class "Default")
      (node (ref "CN1") (pin "A31") (pinfunction "A31_A31") (pintype "passive"))
      (node (ref "U10") (pin "96") (pinfunction "A22_96") (pintype "passive"))
      (node (ref "U11") (pin "57") (pinfunction "CA22_57") (pintype "passive"))
    )
    (net (code "61") (name "/CA23") (class "Default")
      (node (ref "CN1") (pin "A1") (pinfunction "A1_A1") (pintype "passive"))
      (node (ref "U10") (pin "95") (pinfunction "A23_95") (pintype "passive"))
      (node (ref "U11") (pin "56") (pinfunction "CA23_56") (pintype "passive"))
      (node (ref "U12") (pin "45") (pinfunction "NPS2_45") (pintype "passive"))
    )
    (net (code "62") (name "/CD0") (class "Default")
      (node (ref "CN1") (pin "16") (pinfunction "16_16") (pintype "passive"))
      (node (ref "I3") (pin "1") (pinfunction "1_1") (pintype "passive"))
      (node (ref "U11") (pin "101") (pinfunction "CPU-87-D0_101") (pintype "passive"))
      (node (ref "U12") (pin "19") (pinfunction "D0_19") (pintype "passive"))
    )
    (net (code "63") (name "/CD1") (class "Default")
      (node (ref "CN1") (pin "15") (pinfunction "15_15") (pintype "passive"))
      (node (ref "I3") (pin "51") (pinfunction "51_51") (pintype "passive"))
      (node (ref "U11") (pin "102") (pinfunction "CPU-87-D1_102") (pintype "passive"))
      (node (ref "U12") (pin "20") (pinfunction "D1_20") (pintype "passive"))
    )
    (net (code "64") (name "/CD2") (class "Default")
      (node (ref "CN1") (pin "14") (pinfunction "14_14") (pintype "passive"))
      (node (ref "I3") (pin "2") (pinfunction "2_2") (pintype "passive"))
      (node (ref "U11") (pin "103") (pinfunction "CPU-87-D2_103") (pintype "passive"))
      (node (ref "U12") (pin "23") (pinfunction "D2_23") (pintype "passive"))
    )
    (net (code "65") (name "/CD3") (class "Default")
      (node (ref "CN1") (pin "13") (pinfunction "13_13") (pintype "passive"))
      (node (ref "I3") (pin "50") (pinfunction "50_50") (pintype "passive"))
      (node (ref "U11") (pin "104") (pinfunction "CPU-87-D3_104") (pintype "passive"))
      (node (ref "U12") (pin "8") (pinfunction "D3_8") (pintype "passive"))
    )
    (net (code "66") (name "/CD4") (class "Default")
      (node (ref "CN1") (pin "12") (pinfunction "12_12") (pintype "passive"))
      (node (ref "I3") (pin "3") (pinfunction "3_3") (pintype "passive"))
      (node (ref "U11") (pin "105") (pinfunction "CPU-87-D4_105") (pintype "passive"))
      (node (ref "U12") (pin "7") (pinfunction "D4_7") (pintype "passive"))
    )
    (net (code "67") (name "/CD5") (class "Default")
      (node (ref "CN1") (pin "11") (pinfunction "11_11") (pintype "passive"))
      (node (ref "I3") (pin "48") (pinfunction "48_48") (pintype "passive"))
      (node (ref "U11") (pin "109") (pinfunction "CPU-87-D5_109") (pintype "passive"))
      (node (ref "U12") (pin "6") (pinfunction "D5_6") (pintype "passive"))
    )
    (net (code "68") (name "/CD6") (class "Default")
      (node (ref "CN1") (pin "10") (pinfunction "10_10") (pintype "passive"))
      (node (ref "I3") (pin "5") (pinfunction "5_5") (pintype "passive"))
      (node (ref "U11") (pin "110") (pinfunction "CPU-87-D6_110") (pintype "passive"))
      (node (ref "U12") (pin "3") (pinfunction "D6_3") (pintype "passive"))
    )
    (net (code "69") (name "/CD7") (class "Default")
      (node (ref "CN1") (pin "9") (pinfunction "9_9") (pintype "passive"))
      (node (ref "I3") (pin "47") (pinfunction "47_47") (pintype "passive"))
      (node (ref "U11") (pin "111") (pinfunction "CPU-87-D7_111") (pintype "passive"))
      (node (ref "U12") (pin "2") (pinfunction "D7_2") (pintype "passive"))
    )
    (net (code "70") (name "/CD8") (class "Default")
      (node (ref "CN1") (pin "8") (pinfunction "8_8") (pintype "passive"))
      (node (ref "I3") (pin "6") (pinfunction "6_6") (pintype "passive"))
      (node (ref "U11") (pin "113") (pinfunction "CPU-87-D8_113") (pintype "passive"))
      (node (ref "U12") (pin "24") (pinfunction "D8_24") (pintype "passive"))
    )
    (net (code "71") (name "/CD9") (class "Default")
      (node (ref "CN1") (pin "7") (pinfunction "7_7") (pintype "passive"))
      (node (ref "I3") (pin "46") (pinfunction "46_46") (pintype "passive"))
      (node (ref "U11") (pin "115") (pinfunction "CPU-87-D9_115") (pintype "passive"))
      (node (ref "U12") (pin "28") (pinfunction "D9_28") (pintype "passive"))
    )
    (net (code "72") (name "/CD10") (class "Default")
      (node (ref "CN1") (pin "6") (pinfunction "6_6") (pintype "passive"))
      (node (ref "I3") (pin "7") (pinfunction "7_7") (pintype "passive"))
      (node (ref "U11") (pin "116") (pinfunction "CPU-87-D10_116") (pintype "passive"))
      (node (ref "U12") (pin "29") (pinfunction "D10_29") (pintype "passive"))
    )
    (net (code "73") (name "/CD11") (class "Default")
      (node (ref "CN1") (pin "5") (pinfunction "5_5") (pintype "passive"))
      (node (ref "I3") (pin "45") (pinfunction "45_45") (pintype "passive"))
      (node (ref "U11") (pin "117") (pinfunction "CPU-87-D11_117") (pintype "passive"))
      (node (ref "U12") (pin "30") (pinfunction "D11_30") (pintype "passive"))
    )
    (net (code "74") (name "/CD12") (class "Default")
      (node (ref "CN1") (pin "4") (pinfunction "4_4") (pintype "passive"))
      (node (ref "I3") (pin "9") (pinfunction "9_9") (pintype "passive"))
      (node (ref "U11") (pin "121") (pinfunction "CPU-87-D12_121") (pintype "passive"))
      (node (ref "U12") (pin "16") (pinfunction "D12_16") (pintype "passive"))
    )
    (net (code "75") (name "/CD13") (class "Default")
      (node (ref "CN1") (pin "3") (pinfunction "3_3") (pintype "passive"))
      (node (ref "I3") (pin "43") (pinfunction "43_43") (pintype "passive"))
      (node (ref "U11") (pin "122") (pinfunction "CPU-87-D13_122") (pintype "passive"))
      (node (ref "U12") (pin "15") (pinfunction "D13_15") (pintype "passive"))
    )
    (net (code "76") (name "/CD14") (class "Default")
      (node (ref "CN1") (pin "2") (pinfunction "2_2") (pintype "passive"))
      (node (ref "I3") (pin "10") (pinfunction "10_10") (pintype "passive"))
      (node (ref "U11") (pin "123") (pinfunction "CPU-87-D14_123") (pintype "passive"))
      (node (ref "U12") (pin "12") (pinfunction "D14_12") (pintype "passive"))
    )
    (net (code "77") (name "/CD15") (class "Default")
      (node (ref "CN1") (pin "1") (pinfunction "1_1") (pintype "passive"))
      (node (ref "I3") (pin "42") (pinfunction "42_42") (pintype "passive"))
      (node (ref "U11") (pin "124") (pinfunction "CPU-87-D15_124") (pintype "passive"))
      (node (ref "U12") (pin "11") (pinfunction "D15_11") (pintype "passive"))
    )
    (net (code "78") (name "/CPU_*ADS") (class "Default")
      (node (ref "CN1") (pin "26") (pinfunction "26_26") (pintype "passive"))
      (node (ref "U11") (pin "99") (pinfunction "CPU-87-~{ADS}_99") (pintype "passive"))
      (node (ref "U12") (pin "47") (pinfunction "~{ADS}_47") (pintype "passive"))
    )
    (net (code "79") (name "/CPU_*BHE") (class "Default")
      (node (ref "CN1") (pin "28") (pinfunction "28_28") (pintype "passive"))
      (node (ref "U11") (pin "94") (pinfunction "CPU_~{BHE}_94") (pintype "passive"))
    )
    (net (code "80") (name "/CPU_*BLE") (class "Default")
      (node (ref "CN1") (pin "27") (pinfunction "27_27") (pintype "passive"))
      (node (ref "U11") (pin "95") (pinfunction "CPU_~{BLE}_95") (pintype "passive"))
    )
    (net (code "81") (name "/CPU_*BUSY") (class "Default")
      (node (ref "CN1") (pin "A20") (pinfunction "A20_A20") (pintype "passive"))
      (node (ref "U11") (pin "89") (pinfunction "CPU_~{BUSY}_89") (pintype "passive"))
    )
    (net (code "82") (name "/CPU_*READY") (class "Default")
      (node (ref "CN1") (pin "21") (pinfunction "21_21") (pintype "passive"))
      (node (ref "U11") (pin "98") (pinfunction "CPU-87-~{READY}_98") (pintype "passive"))
      (node (ref "U12") (pin "49") (pinfunction "~{READY}_49") (pintype "passive"))
    )
    (net (code "83") (name "/CPU_D{slash}*C") (class "Default")
      (node (ref "CN1") (pin "A29") (pinfunction "A29_A29") (pintype "passive"))
      (node (ref "U10") (pin "61") (pinfunction "~{DMAMEMR}_61") (pintype "passive"))
      (node (ref "U11") (pin "91") (pinfunction "CPU_D/~{C}_91") (pintype "passive"))
    )
    (net (code "84") (name "/CPU_HLDA") (class "Default")
      (node (ref "CN1") (pin "30") (pinfunction "30_30") (pintype "passive"))
      (node (ref "U11") (pin "45") (pinfunction "CPU_HLDA_45") (pintype "passive"))
    )
    (net (code "85") (name "/CPU_HOLD") (class "Default")
      (node (ref "CN1") (pin "31") (pinfunction "31_31") (pintype "passive"))
      (node (ref "U18") (pin "4") (pinfunction "Q_4") (pintype "output"))
    )
    (net (code "86") (name "/CPU_INTR") (class "Default")
      (node (ref "CN1") (pin "29") (pinfunction "29_29") (pintype "passive"))
      (node (ref "U10") (pin "73") (pinfunction "INTR_73") (pintype "passive"))
    )
    (net (code "87") (name "/CPU_M{slash}*IO") (class "Default")
      (node (ref "CN1") (pin "A3") (pinfunction "A3_A3") (pintype "passive"))
      (node (ref "U11") (pin "92") (pinfunction "CPU_M/~{IO}_92") (pintype "passive"))
      (node (ref "U12") (pin "44") (pinfunction "~{NPS1}_44") (pintype "passive"))
    )
    (net (code "88") (name "/CPU_NMI") (class "Default")
      (node (ref "CN1") (pin "A18") (pinfunction "A18_A18") (pintype "passive"))
      (node (ref "U11") (pin "83") (pinfunction "CPU_NMI_83") (pintype "passive"))
    )
    (net (code "89") (name "/CPU_PEREQ") (class "Default")
      (node (ref "CN1") (pin "A16") (pinfunction "A16_A16") (pintype "passive"))
      (node (ref "U11") (pin "88") (pinfunction "CPU_PEREQ_88") (pintype "passive"))
    )
    (net (code "90") (name "/CPU_RESET") (class "Default")
      (node (ref "CN1") (pin "A15") (pinfunction "A15_A15") (pintype "passive"))
      (node (ref "U11") (pin "84") (pinfunction "CPU_RESET_84") (pintype "passive"))
    )
    (net (code "91") (name "/CPU_W{slash}*R") (class "Default")
      (node (ref "CN1") (pin "A9") (pinfunction "A9_A9") (pintype "passive"))
      (node (ref "U10") (pin "62") (pinfunction "~{DMAMEMW}_62") (pintype "passive"))
      (node (ref "U11") (pin "90") (pinfunction "CPU_W/~{R}_90") (pintype "passive"))
      (node (ref "U12") (pin "41") (pinfunction "W/~{R}_41") (pintype "passive"))
    )
    (net (code "92") (name "/D245_*OE") (class "Default")
      (node (ref "U11") (pin "149") (pinfunction "D245-~{OE}_149") (pintype "passive"))
      (node (ref "UD1") (pin "19") (pinfunction "~{OE}_19") (pintype "input"))
    )
    (net (code "93") (name "/D245_DIR") (class "Default")
      (node (ref "U11") (pin "185") (pinfunction "D245-DIR_185") (pintype "passive"))
      (node (ref "UD1") (pin "1") (pinfunction "DIR_1") (pintype "input"))
    )
    (net (code "94") (name "/DRAM_DP0") (class "Default")
      (node (ref "U11") (pin "112") (pinfunction "DRAM_DP0_112") (pintype "passive"))
    )
    (net (code "95") (name "/DRAM_DP1") (class "Default")
      (node (ref "U11") (pin "125") (pinfunction "DRAM_DP1_125") (pintype "passive"))
    )
    (net (code "96") (name "/FS0") (class "Default")
      (node (ref "R5") (pin "1") (pinfunction "1_1") (pintype "passive"))
      (node (ref "U3") (pin "1") (pinfunction "FS0_1") (pintype "passive"))
    )
    (net (code "97") (name "/FS1") (class "Default")
      (node (ref "R1") (pin "1") (pinfunction "1_1") (pintype "passive"))
      (node (ref "U3") (pin "5") (pinfunction "FS1_5") (pintype "passive"))
    )
    (net (code "98") (name "/ISAC_*BHE") (class "Default")
      (node (ref "I2") (pin "15") (pinfunction "15_15") (pintype "passive"))
      (node (ref "U11") (pin "24") (pinfunction "ISAC_~{BHE}_24") (pintype "passive"))
    )
    (net (code "99") (name "/ISAC_*MEMR") (class "Default")
      (node (ref "I2") (pin "34") (pinfunction "34_34") (pintype "passive"))
      (node (ref "R34") (pin "2") (pinfunction "2_2") (pintype "passive"))
      (node (ref "U11") (pin "31") (pinfunction "ISAC_~{MEMR}_31") (pintype "passive"))
      (node (ref "U17") (pin "32") (pinfunction "~{OE}_32") (pintype "passive"))
    )
    (net (code "100") (name "/ISAC_*MEMW") (class "Default")
      (node (ref "I2") (pin "19") (pinfunction "19_19") (pintype "passive"))
      (node (ref "R35") (pin "2") (pinfunction "2_2") (pintype "passive"))
      (node (ref "U11") (pin "32") (pinfunction "ISAC_~{MEMW}_32") (pintype "passive"))
    )
    (net (code "101") (name "/ISAC_A17") (class "Default")
      (node (ref "I2") (pin "31") (pinfunction "31_31") (pintype "passive"))
      (node (ref "U11") (pin "37") (pinfunction "ISA_A17_37") (pintype "passive"))
    )
    (net (code "102") (name "/ISAC_A18") (class "Default")
      (node (ref "I2") (pin "21") (pinfunction "21_21") (pintype "passive"))
      (node (ref "U11") (pin "36") (pinfunction "ISA_A18_36") (pintype "passive"))
    )
    (net (code "103") (name "/ISAC_A19") (class "Default")
      (node (ref "I2") (pin "32") (pinfunction "32_32") (pintype "passive"))
      (node (ref "U11") (pin "35") (pinfunction "ISA_A19_35") (pintype "passive"))
    )
    (net (code "104") (name "/ISAC_A20") (class "Default")
      (node (ref "I2") (pin "18") (pinfunction "18_18") (pintype "passive"))
      (node (ref "U11") (pin "30") (pinfunction "ISA_A20_30") (pintype "passive"))
    )
    (net (code "105") (name "/ISAC_A21") (class "Default")
      (node (ref "I2") (pin "35") (pinfunction "35_35") (pintype "passive"))
      (node (ref "U11") (pin "29") (pinfunction "IAS_A21_29") (pintype "passive"))
    )
    (net (code "106") (name "/ISAC_A22") (class "Default")
      (node (ref "I2") (pin "17") (pinfunction "17_17") (pintype "passive"))
      (node (ref "U11") (pin "28") (pinfunction "ISA_A22_28") (pintype "passive"))
    )
    (net (code "107") (name "/ISAC_A23") (class "Default")
      (node (ref "I2") (pin "37") (pinfunction "37_37") (pintype "passive"))
      (node (ref "U11") (pin "25") (pinfunction "ISA_A23_25") (pintype "passive"))
    )
    (net (code "108") (name "/ISAD_*DACK0") (class "Default")
      (node (ref "I1") (pin "13") (pinfunction "13_13") (pintype "passive"))
      (node (ref "U10") (pin "46") (pinfunction "DACK0_46") (pintype "passive"))
    )
    (net (code "109") (name "/ISAD_*DACK5") (class "Default")
      (node (ref "I1") (pin "37") (pinfunction "37_37") (pintype "passive"))
      (node (ref "U10") (pin "57") (pinfunction "DACK5_57") (pintype "passive"))
    )
    (net (code "110") (name "/ISAD_*DACK6") (class "Default")
      (node (ref "I1") (pin "15") (pinfunction "15_15") (pintype "passive"))
      (node (ref "U10") (pin "56") (pinfunction "DACK6_56") (pintype "passive"))
    )
    (net (code "111") (name "/ISAD_*DACK7") (class "Default")
      (node (ref "I1") (pin "38") (pinfunction "38_38") (pintype "passive"))
      (node (ref "U10") (pin "55") (pinfunction "DACK7_55") (pintype "passive"))
    )
    (net (code "112") (name "/ISAD_*IOCS16") (class "Default")
      (node (ref "I2") (pin "3") (pinfunction "3_3") (pintype "passive"))
      (node (ref "R36") (pin "2") (pinfunction "2_2") (pintype "passive"))
      (node (ref "U11") (pin "186") (pinfunction "ISAD_~{IOCS16}_186") (pintype "passive"))
    )
    (net (code "113") (name "/ISAD_*MASTER") (class "Default")
      (node (ref "I2") (pin "8") (pinfunction "8_8") (pintype "passive"))
      (node (ref "R38") (pin "2") (pinfunction "2_2") (pintype "passive"))
      (node (ref "U11") (pin "193") (pinfunction "ISAD_~{MASTER}_193") (pintype "passive"))
    )
    (net (code "114") (name "/ISAD_*MEMCS16") (class "Default")
      (node (ref "I2") (pin "1") (pinfunction "1_1") (pintype "passive"))
      (node (ref "R37") (pin "2") (pinfunction "2_2") (pintype "passive"))
      (node (ref "U11") (pin "206") (pinfunction "ISAD_~{MEMCS16}_206") (pintype "passive"))
    )
    (net (code "115") (name "/ISAD_DRQ0") (class "Default")
      (node (ref "I1") (pin "10") (pinfunction "10_10") (pintype "passive"))
      (node (ref "U10") (pin "42") (pinfunction "DREQ0_42") (pintype "passive"))
    )
    (net (code "116") (name "/ISAD_DRQ5") (class "Default")
      (node (ref "I1") (pin "17") (pinfunction "17_17") (pintype "passive"))
      (node (ref "U10") (pin "60") (pinfunction "DREQ5_60") (pintype "passive"))
    )
    (net (code "117") (name "/ISAD_DRQ6") (class "Default")
      (node (ref "I1") (pin "36") (pinfunction "36_36") (pintype "passive"))
      (node (ref "U10") (pin "59") (pinfunction "DREQ6_59") (pintype "passive"))
    )
    (net (code "118") (name "/ISAD_DRQ7") (class "Default")
      (node (ref "I1") (pin "16") (pinfunction "16_16") (pintype "passive"))
      (node (ref "U10") (pin "58") (pinfunction "DREQ7_58") (pintype "passive"))
    )
    (net (code "119") (name "/ISAD_IRQ10") (class "Default")
      (node (ref "I1") (pin "29") (pinfunction "29_29") (pintype "passive"))
      (node (ref "R14") (pin "2") (pinfunction "2_2") (pintype "passive"))
      (node (ref "U10") (pin "84") (pinfunction "IRQ10_84") (pintype "passive"))
    )
    (net (code "120") (name "/ISAD_IRQ11") (class "Default")
      (node (ref "I1") (pin "24") (pinfunction "24_24") (pintype "passive"))
      (node (ref "R15") (pin "2") (pinfunction "2_2") (pintype "passive"))
      (node (ref "U10") (pin "83") (pinfunction "IRQ11_83") (pintype "passive"))
    )
    (net (code "121") (name "/ISAD_IRQ12") (class "Default")
      (node (ref "I1") (pin "28") (pinfunction "28_28") (pintype "passive"))
      (node (ref "R16") (pin "2") (pinfunction "2_2") (pintype "passive"))
      (node (ref "U10") (pin "82") (pinfunction "IRQ12_82") (pintype "passive"))
    )
    (net (code "122") (name "/ISAD_IRQ14") (class "Default")
      (node (ref "I1") (pin "31") (pinfunction "31_31") (pintype "passive"))
      (node (ref "R17") (pin "2") (pinfunction "2_2") (pintype "passive"))
      (node (ref "U10") (pin "80") (pinfunction "IRQ14_80") (pintype "passive"))
    )
    (net (code "123") (name "/ISAD_IRQ15") (class "Default")
      (node (ref "I1") (pin "21") (pinfunction "21_21") (pintype "passive"))
      (node (ref "R19") (pin "2") (pinfunction "2_2") (pintype "passive"))
      (node (ref "U10") (pin "79") (pinfunction "IRQ15_79") (pintype "passive"))
    )
    (net (code "124") (name "/ISA_*DACK0") (class "Default")
      (node (ref "I2") (pin "47") (pinfunction "47_47") (pintype "passive"))
      (node (ref "R39") (pin "2") (pinfunction "2_2") (pintype "passive"))
      (node (ref "U11") (pin "192") (pinfunction "ISA_~{DACK0}_192") (pintype "passive"))
    )
    (net (code "125") (name "/ISA_*DACK1") (class "Default")
      (node (ref "I1") (pin "40") (pinfunction "40_40") (pintype "passive"))
      (node (ref "U10") (pin "47") (pinfunction "DACK1_47") (pintype "passive"))
    )
    (net (code "126") (name "/ISA_*DACK2") (class "Default")
      (node (ref "I1") (pin "12") (pinfunction "12_12") (pintype "passive"))
      (node (ref "U10") (pin "48") (pinfunction "DACK2_48") (pintype "passive"))
    )
    (net (code "127") (name "/ISA_*DACK3") (class "Default")
      (node (ref "I1") (pin "41") (pinfunction "41_41") (pintype "passive"))
      (node (ref "U10") (pin "49") (pinfunction "DACK3_49") (pintype "passive"))
    )
    (net (code "128") (name "/ISA_*IOCHCK") (class "Default")
      (node (ref "I2") (pin "45") (pinfunction "45_45") (pintype "passive"))
      (node (ref "R41") (pin "2") (pinfunction "2_2") (pintype "passive"))
      (node (ref "U11") (pin "9") (pinfunction "ISA_~{IOCHCK}_9") (pintype "passive"))
    )
    (net (code "129") (name "/ISA_*IOR") (class "Default")
      (node (ref "I2") (pin "49") (pinfunction "49_49") (pintype "passive"))
      (node (ref "R30") (pin "2") (pinfunction "2_2") (pintype "passive"))
      (node (ref "U11") (pin "197") (pinfunction "ISA_~{IOR}_197") (pintype "passive"))
    )
    (net (code "130") (name "/ISA_*IOW") (class "Default")
      (node (ref "I2") (pin "50") (pinfunction "50_50") (pintype "passive"))
      (node (ref "R31") (pin "2") (pinfunction "2_2") (pintype "passive"))
      (node (ref "U11") (pin "198") (pinfunction "ISA_~{IOW}_198") (pintype "passive"))
    )
    (net (code "131") (name "/ISA_*MEMR") (class "Default")
      (node (ref "I2") (pin "48") (pinfunction "48_48") (pintype "passive"))
      (node (ref "R32") (pin "2") (pinfunction "2_2") (pintype "passive"))
      (node (ref "U11") (pin "190") (pinfunction "ISA_~{MEMR}_190") (pintype "passive"))
    )
    (net (code "132") (name "/ISA_*MEMW") (class "Default")
      (node (ref "I2") (pin "5") (pinfunction "5_5") (pintype "passive"))
      (node (ref "R33") (pin "2") (pinfunction "2_2") (pintype "passive"))
      (node (ref "U11") (pin "191") (pinfunction "ISA_~{MEMW}_191") (pintype "passive"))
    )
    (net (code "133") (name "/ISA_A0") (class "Default")
      (node (ref "I1") (pin "43") (pinfunction "43_43") (pintype "passive"))
      (node (ref "U11") (pin "187") (pinfunction "ISA_A0_187") (pintype "passive"))
      (node (ref "U17") (pin "20") (pinfunction "A0_20") (pintype "passive"))
    )
    (net (code "134") (name "/ISA_A1") (class "Default")
      (node (ref "I1") (pin "44") (pinfunction "44_44") (pintype "passive"))
      (node (ref "U10") (pin "39") (pinfunction "XA1_39") (pintype "passive"))
      (node (ref "U11") (pin "172") (pinfunction "206_A1_172") (pintype "passive"))
      (node (ref "U17") (pin "19") (pinfunction "A1_19") (pintype "passive"))
    )
    (net (code "135") (name "/ISA_A2") (class "Default")
      (node (ref "I1") (pin "45") (pinfunction "45_45") (pintype "passive"))
      (node (ref "U10") (pin "38") (pinfunction "XA2_38") (pintype "passive"))
      (node (ref "U11") (pin "173") (pinfunction "206_A2_173") (pintype "passive"))
      (node (ref "U17") (pin "18") (pinfunction "A2_18") (pintype "passive"))
    )
    (net (code "136") (name "/ISA_A3") (class "Default")
      (node (ref "I1") (pin "46") (pinfunction "46_46") (pintype "passive"))
      (node (ref "U10") (pin "37") (pinfunction "XA3_37") (pintype "passive"))
      (node (ref "U11") (pin "174") (pinfunction "206_A3_174") (pintype "passive"))
      (node (ref "U17") (pin "17") (pinfunction "A3_17") (pintype "passive"))
    )
    (net (code "137") (name "/ISA_A4") (class "Default")
      (node (ref "I1") (pin "47") (pinfunction "47_47") (pintype "passive"))
      (node (ref "U10") (pin "36") (pinfunction "XA4_36") (pintype "passive"))
      (node (ref "U11") (pin "175") (pinfunction "206_A4_175") (pintype "passive"))
      (node (ref "U17") (pin "16") (pinfunction "A4_16") (pintype "passive"))
    )
    (net (code "138") (name "/ISA_A5") (class "Default")
      (node (ref "I1") (pin "9") (pinfunction "9_9") (pintype "passive"))
      (node (ref "U10") (pin "35") (pinfunction "XA5_35") (pintype "passive"))
      (node (ref "U11") (pin "177") (pinfunction "206_A5_177") (pintype "passive"))
      (node (ref "U17") (pin "15") (pinfunction "A5_15") (pintype "passive"))
    )
    (net (code "139") (name "/ISA_A6") (class "Default")
      (node (ref "I1") (pin "8") (pinfunction "8_8") (pintype "passive"))
      (node (ref "U10") (pin "34") (pinfunction "XA6_34") (pintype "passive"))
      (node (ref "U11") (pin "178") (pinfunction "206_A6_178") (pintype "passive"))
      (node (ref "U17") (pin "14") (pinfunction "A6_14") (pintype "passive"))
    )
    (net (code "140") (name "/ISA_A7") (class "Default")
      (node (ref "I1") (pin "7") (pinfunction "7_7") (pintype "passive"))
      (node (ref "U10") (pin "33") (pinfunction "XA7_33") (pintype "passive"))
      (node (ref "U11") (pin "179") (pinfunction "206_A7_179") (pintype "passive"))
      (node (ref "U17") (pin "13") (pinfunction "A7_13") (pintype "passive"))
    )
    (net (code "141") (name "/ISA_A8") (class "Default")
      (node (ref "I1") (pin "6") (pinfunction "6_6") (pintype "passive"))
      (node (ref "U10") (pin "32") (pinfunction "XA8_32") (pintype "passive"))
      (node (ref "U11") (pin "180") (pinfunction "206_A8_180") (pintype "passive"))
      (node (ref "U17") (pin "3") (pinfunction "A8_3") (pintype "passive"))
    )
    (net (code "142") (name "/ISA_A9") (class "Default")
      (node (ref "I2") (pin "38") (pinfunction "38_38") (pintype "passive"))
      (node (ref "U10") (pin "31") (pinfunction "XA9_31") (pintype "passive"))
      (node (ref "U11") (pin "23") (pinfunction "SA9_23") (pintype "passive"))
      (node (ref "U17") (pin "2") (pinfunction "A9_2") (pintype "passive"))
    )
    (net (code "143") (name "/ISA_A10") (class "Default")
      (node (ref "I2") (pin "14") (pinfunction "14_14") (pintype "passive"))
      (node (ref "U11") (pin "22") (pinfunction "SA10_22") (pintype "passive"))
      (node (ref "U17") (pin "31") (pinfunction "A10_31") (pintype "passive"))
    )
    (net (code "144") (name "/ISA_A11") (class "Default")
      (node (ref "I2") (pin "12") (pinfunction "12_12") (pintype "passive"))
      (node (ref "U11") (pin "18") (pinfunction "SA11_18") (pintype "passive"))
      (node (ref "U17") (pin "1") (pinfunction "A11_1") (pintype "passive"))
    )
    (net (code "145") (name "/ISA_A12") (class "Default")
      (node (ref "I2") (pin "41") (pinfunction "41_41") (pintype "passive"))
      (node (ref "U11") (pin "17") (pinfunction "SA12_17") (pintype "passive"))
      (node (ref "U17") (pin "12") (pinfunction "A12_12") (pintype "passive"))
    )
    (net (code "146") (name "/ISA_A13") (class "Default")
      (node (ref "I2") (pin "11") (pinfunction "11_11") (pintype "passive"))
      (node (ref "U11") (pin "16") (pinfunction "SA13_16") (pintype "passive"))
      (node (ref "U17") (pin "4") (pinfunction "A13_4") (pintype "passive"))
    )
    (net (code "147") (name "/ISA_A14") (class "Default")
      (node (ref "I2") (pin "10") (pinfunction "10_10") (pintype "passive"))
      (node (ref "U11") (pin "14") (pinfunction "SA14_14") (pintype "passive"))
      (node (ref "U17") (pin "5") (pinfunction "A14_5") (pintype "passive"))
    )
    (net (code "148") (name "/ISA_A15") (class "Default")
      (node (ref "I2") (pin "43") (pinfunction "43_43") (pintype "passive"))
      (node (ref "U11") (pin "13") (pinfunction "SA15_13") (pintype "passive"))
      (node (ref "U17") (pin "11") (pinfunction "A15_11") (pintype "passive"))
    )
    (net (code "149") (name "/ISA_A16") (class "Default")
      (node (ref "I2") (pin "9") (pinfunction "9_9") (pintype "passive"))
      (node (ref "U11") (pin "12") (pinfunction "SA16_12") (pintype "passive"))
    )
    (net (code "150") (name "/ISA_A17") (class "Default")
      (node (ref "I2") (pin "7") (pinfunction "7_7") (pintype "passive"))
      (node (ref "U11") (pin "8") (pinfunction "SA17_8") (pintype "passive"))
    )
    (net (code "151") (name "/ISA_A18") (class "Default")
      (node (ref "I2") (pin "46") (pinfunction "46_46") (pintype "passive"))
      (node (ref "U11") (pin "7") (pinfunction "SA18_7") (pintype "passive"))
    )
    (net (code "152") (name "/ISA_A19") (class "Default")
      (node (ref "I2") (pin "6") (pinfunction "6_6") (pintype "passive"))
      (node (ref "U11") (pin "6") (pinfunction "SA19_6") (pintype "passive"))
    )
    (net (code "153") (name "/ISA_AEN") (class "Default")
      (node (ref "I2") (pin "2") (pinfunction "2_2") (pintype "passive"))
      (node (ref "U11") (pin "205") (pinfunction "ISA_AEN_205") (pintype "passive"))
    )
    (net (code "154") (name "/ISA_ALE") (class "Default")
      (node (ref "I2") (pin "51") (pinfunction "51_51") (pintype "passive"))
      (node (ref "U11") (pin "199") (pinfunction "ISA_ALE_199") (pintype "passive"))
    )
    (net (code "155") (name "/ISA_B8") (class "Default")
      (node (ref "I2") (pin "4") (pinfunction "4_4") (pintype "passive"))
      (node (ref "R29") (pin "2") (pinfunction "2_2") (pintype "passive"))
      (node (ref "U11") (pin "188") (pinfunction "ISA_B8_188") (pintype "passive"))
    )
    (net (code "156") (name "/ISA_CLK86") (class "Default")
      (node (ref "I2") (pin "13") (pinfunction "13_13") (pintype "passive"))
      (node (ref "U10") (pin "15") (pinfunction "SYSCLK_15") (pintype "passive"))
      (node (ref "U11") (pin "20") (pinfunction "ISA_CLK86_20") (pintype "passive"))
    )
    (net (code "157") (name "/ISA_D0") (class "Default")
      (node (ref "I1") (pin "48") (pinfunction "48_48") (pintype "passive"))
      (node (ref "UD1") (pin "9") (pinfunction "A7_9") (pintype "bidirectional"))
    )
    (net (code "158") (name "/ISA_D1") (class "Default")
      (node (ref "I1") (pin "4") (pinfunction "4_4") (pintype "passive"))
      (node (ref "UD1") (pin "8") (pinfunction "A6_8") (pintype "bidirectional"))
    )
    (net (code "159") (name "/ISA_D2") (class "Default")
      (node (ref "I1") (pin "49") (pinfunction "49_49") (pintype "passive"))
      (node (ref "UD1") (pin "7") (pinfunction "A5_7") (pintype "bidirectional"))
    )
    (net (code "160") (name "/ISA_D3") (class "Default")
      (node (ref "I1") (pin "3") (pinfunction "3_3") (pintype "passive"))
      (node (ref "UD1") (pin "6") (pinfunction "A4_6") (pintype "bidirectional"))
    )
    (net (code "161") (name "/ISA_D4") (class "Default")
      (node (ref "I1") (pin "50") (pinfunction "50_50") (pintype "passive"))
      (node (ref "UD1") (pin "5") (pinfunction "A3_5") (pintype "bidirectional"))
    )
    (net (code "162") (name "/ISA_D5") (class "Default")
      (node (ref "I1") (pin "2") (pinfunction "2_2") (pintype "passive"))
      (node (ref "UD1") (pin "4") (pinfunction "A2_4") (pintype "bidirectional"))
    )
    (net (code "163") (name "/ISA_D6") (class "Default")
      (node (ref "I1") (pin "51") (pinfunction "51_51") (pintype "passive"))
      (node (ref "UD1") (pin "3") (pinfunction "A1_3") (pintype "bidirectional"))
    )
    (net (code "164") (name "/ISA_D7") (class "Default")
      (node (ref "I1") (pin "1") (pinfunction "1_1") (pintype "passive"))
      (node (ref "UD1") (pin "2") (pinfunction "A0_2") (pintype "bidirectional"))
    )
    (net (code "165") (name "/ISA_D8") (class "Default")
      (node (ref "I2") (pin "33") (pinfunction "33_33") (pintype "passive"))
      (node (ref "U11") (pin "33") (pinfunction "ISA_D8_33") (pintype "passive"))
    )
    (net (code "166") (name "/ISA_D9") (class "Default")
      (node (ref "I2") (pin "20") (pinfunction "20_20") (pintype "passive"))
      (node (ref "U11") (pin "34") (pinfunction "ISA_D9_34") (pintype "passive"))
    )
    (net (code "167") (name "/ISA_D10") (class "Default")
      (node (ref "I2") (pin "30") (pinfunction "30_30") (pintype "passive"))
      (node (ref "U11") (pin "39") (pinfunction "ISA_D10_39") (pintype "passive"))
    )
    (net (code "168") (name "/ISA_D11") (class "Default")
      (node (ref "I2") (pin "23") (pinfunction "23_23") (pintype "passive"))
      (node (ref "U11") (pin "40") (pinfunction "ISA_D11_40") (pintype "passive"))
    )
    (net (code "169") (name "/ISA_D12") (class "Default")
      (node (ref "I2") (pin "29") (pinfunction "29_29") (pintype "passive"))
      (node (ref "U11") (pin "41") (pinfunction "ISA_D12_41") (pintype "passive"))
    )
    (net (code "170") (name "/ISA_D13") (class "Default")
      (node (ref "I2") (pin "25") (pinfunction "25_25") (pintype "passive"))
      (node (ref "U11") (pin "47") (pinfunction "ISA_D13_47") (pintype "passive"))
    )
    (net (code "171") (name "/ISA_D14") (class "Default")
      (node (ref "I2") (pin "27") (pinfunction "27_27") (pintype "passive"))
      (node (ref "U11") (pin "48") (pinfunction "ISA_D14_48") (pintype "passive"))
    )
    (net (code "172") (name "/ISA_D15") (class "Default")
      (node (ref "I2") (pin "26") (pinfunction "26_26") (pintype "passive"))
      (node (ref "U11") (pin "49") (pinfunction "IDA_D15_49") (pintype "passive"))
    )
    (net (code "173") (name "/ISA_DRQ1") (class "Default")
      (node (ref "I1") (pin "42") (pinfunction "42_42") (pintype "passive"))
      (node (ref "U10") (pin "43") (pinfunction "DREQ1_43") (pintype "passive"))
    )
    (net (code "174") (name "/ISA_DRQ2") (class "Default")
      (node (ref "I1") (pin "14") (pinfunction "14_14") (pintype "passive"))
      (node (ref "U10") (pin "44") (pinfunction "DREQ2_44") (pintype "passive"))
    )
    (net (code "175") (name "/ISA_DRQ3") (class "Default")
      (node (ref "I1") (pin "39") (pinfunction "39_39") (pintype "passive"))
      (node (ref "U10") (pin "45") (pinfunction "DREQ3_45") (pintype "passive"))
    )
    (net (code "176") (name "/ISA_IOREADY") (class "Default")
      (node (ref "I1") (pin "33") (pinfunction "33_33") (pintype "passive"))
      (node (ref "R40") (pin "2") (pinfunction "2_2") (pintype "passive"))
      (node (ref "U10") (pin "71") (pinfunction "IOCHRDY_71") (pintype "passive"))
      (node (ref "U11") (pin "207") (pinfunction "ISA_IOREADY_207") (pintype "passive"))
    )
    (net (code "177") (name "/ISA_IRQ2") (class "Default")
      (node (ref "I1") (pin "23") (pinfunction "23_23") (pintype "passive"))
      (node (ref "R42") (pin "2") (pinfunction "2_2") (pintype "passive"))
      (node (ref "U10") (pin "85") (pinfunction "IRQ9_85") (pintype "passive"))
    )
    (net (code "178") (name "/ISA_IRQ3") (class "Default")
      (node (ref "I1") (pin "26") (pinfunction "26_26") (pintype "passive"))
      (node (ref "R43") (pin "2") (pinfunction "2_2") (pintype "passive"))
      (node (ref "U10") (pin "93") (pinfunction "IRQ3_93") (pintype "passive"))
    )
    (net (code "179") (name "/ISA_IRQ4") (class "Default")
      (node (ref "I1") (pin "27") (pinfunction "27_27") (pintype "passive"))
      (node (ref "R44") (pin "2") (pinfunction "2_2") (pintype "passive"))
      (node (ref "U10") (pin "92") (pinfunction "IRQ4_92") (pintype "passive"))
    )
    (net (code "180") (name "/ISA_IRQ5") (class "Default")
      (node (ref "I1") (pin "25") (pinfunction "25_25") (pintype "passive"))
      (node (ref "R45") (pin "2") (pinfunction "2_2") (pintype "passive"))
      (node (ref "U10") (pin "91") (pinfunction "IRQ5_91") (pintype "passive"))
    )
    (net (code "181") (name "/ISA_IRQ6") (class "Default")
      (node (ref "I1") (pin "22") (pinfunction "22_22") (pintype "passive"))
      (node (ref "R46") (pin "2") (pinfunction "2_2") (pintype "passive"))
      (node (ref "U10") (pin "87") (pinfunction "IRQ6_87") (pintype "passive"))
    )
    (net (code "182") (name "/ISA_IRQ7") (class "Default")
      (node (ref "I1") (pin "30") (pinfunction "30_30") (pintype "passive"))
      (node (ref "R47") (pin "2") (pinfunction "2_2") (pintype "passive"))
      (node (ref "U10") (pin "86") (pinfunction "IRQ7_86") (pintype "passive"))
    )
    (net (code "183") (name "/ISA_OSC") (class "Default")
      (node (ref "I1") (pin "11") (pinfunction "11_11") (pintype "passive"))
      (node (ref "U11") (pin "159") (pinfunction "ISA_OSC_159") (pintype "passive"))
      (node (ref "U11") (pin "160") (pinfunction "ISA_OSC_160") (pintype "passive"))
    )
    (net (code "184") (name "/ISA_RESET") (class "Default")
      (node (ref "C1") (pin "1") (pinfunction "1_1") (pintype "passive"))
      (node (ref "I1") (pin "34") (pinfunction "34_34") (pintype "passive"))
      (node (ref "U10") (pin "10") (pinfunction "RESET_10") (pintype "passive"))
      (node (ref "U11") (pin "145") (pinfunction "ISA-206-RESET_145") (pintype "passive"))
    )
    (net (code "185") (name "/ISA_T{slash}C") (class "Default")
      (node (ref "I1") (pin "19") (pinfunction "19_19") (pintype "passive"))
      (node (ref "U10") (pin "70") (pinfunction "TC_70") (pintype "passive"))
    )
    (net (code "186") (name "/J5_386{slash}486") (class "Default")
      (node (ref "JPx") (pin "1") (pinfunction "1_1") (pintype "passive"))
      (node (ref "U11") (pin "82") (pinfunction "J5-386/486_82") (pintype "passive"))
      (node (ref "U16") (pin "13") (pintype "input"))
    )
    (net (code "187") (name "/KEY_A") (class "Default")
      (node (ref "I1") (pin "18") (pinfunction "18_18") (pintype "passive"))
      (node (ref "U11") (pin "136") (pinfunction "KEY_A_136") (pintype "passive"))
    )
    (net (code "188") (name "/KEY_B") (class "Default")
      (node (ref "I1") (pin "35") (pinfunction "35_35") (pintype "passive"))
      (node (ref "U11") (pin "137") (pinfunction "KEY_B_137") (pintype "passive"))
    )
    (net (code "189") (name "/MA0") (class "Default")
      (node (ref "I3") (pin "28") (pinfunction "28_28") (pintype "passive"))
      (node (ref "U11") (pin "153") (pinfunction "MAA0_153") (pintype "passive"))
    )
    (net (code "190") (name "/MA1") (class "Default")
      (node (ref "I3") (pin "24") (pinfunction "24_24") (pintype "passive"))
      (node (ref "U11") (pin "152") (pinfunction "MAA1_152") (pintype "passive"))
    )
    (net (code "191") (name "/MA2") (class "Default")
      (node (ref "I3") (pin "29") (pinfunction "29_29") (pintype "passive"))
      (node (ref "U11") (pin "151") (pinfunction "MAA2_151") (pintype "passive"))
    )
    (net (code "192") (name "/MA3") (class "Default")
      (node (ref "I3") (pin "20") (pinfunction "20_20") (pintype "passive"))
      (node (ref "U11") (pin "144") (pinfunction "MAA3_144") (pintype "passive"))
    )
    (net (code "193") (name "/MA4") (class "Default")
      (node (ref "I3") (pin "33") (pinfunction "33_33") (pintype "passive"))
      (node (ref "U11") (pin "143") (pinfunction "MAA4_143") (pintype "passive"))
    )
    (net (code "194") (name "/MA5") (class "Default")
      (node (ref "I3") (pin "18") (pinfunction "18_18") (pintype "passive"))
      (node (ref "U11") (pin "139") (pinfunction "MAA5_139") (pintype "passive"))
    )
    (net (code "195") (name "/MA6") (class "Default")
      (node (ref "I3") (pin "35") (pinfunction "35_35") (pintype "passive"))
      (node (ref "U11") (pin "138") (pinfunction "MAA6_138") (pintype "passive"))
    )
    (net (code "196") (name "/MA7") (class "Default")
      (node (ref "I3") (pin "15") (pinfunction "15_15") (pintype "passive"))
      (node (ref "U11") (pin "133") (pinfunction "MAA7_133") (pintype "passive"))
    )
    (net (code "197") (name "/MA8") (class "Default")
      (node (ref "I3") (pin "38") (pinfunction "38_38") (pintype "passive"))
      (node (ref "U11") (pin "132") (pinfunction "MAA8_132") (pintype "passive"))
    )
    (net (code "198") (name "/MA9") (class "Default")
      (node (ref "I3") (pin "12") (pinfunction "12_12") (pintype "passive"))
      (node (ref "U11") (pin "127") (pinfunction "MAA9_127") (pintype "passive"))
    )
    (net (code "199") (name "/MA10") (class "Default")
      (node (ref "I3") (pin "41") (pinfunction "41_41") (pintype "passive"))
      (node (ref "U11") (pin "126") (pinfunction "MAA10_126") (pintype "passive"))
    )
    (net (code "200") (name "/PIPELINE") (class "Default")
      (node (ref "CN1") (pin "20") (pinfunction "20_20") (pintype "passive"))
    )
    (net (code "201") (name "/POWERGOOD") (class "Default")
      (node (ref "C9") (pin "1") (pinfunction "1_1") (pintype "passive"))
      (node (ref "RR") (pin "1") (pinfunction "1_1") (pintype "passive"))
      (node (ref "U10") (pin "6") (pinfunction "PWRGD_6") (pintype "passive"))
      (node (ref "U11") (pin "146") (pinfunction "POWERGOOD_146") (pintype "passive"))
    )
    (net (code "202") (name "/ROM_*CS") (class "Default")
      (node (ref "U11") (pin "19") (pinfunction "ROM_*CS_19") (pintype "passive"))
      (node (ref "U17") (pin "30") (pinfunction "~{CE}_30") (pintype "passive"))
    )
    (net (code "203") (name "/SD0") (class "Default")
      (node (ref "U10") (pin "25") (pinfunction "XD0_25") (pintype "passive"))
      (node (ref "U11") (pin "5") (pinfunction "SD0_5") (pintype "passive"))
      (node (ref "U17") (pin "21") (pinfunction "I/O0_21") (pintype "passive"))
      (node (ref "UD1") (pin "11") (pinfunction "B7_11") (pintype "bidirectional"))
    )
    (net (code "204") (name "/SD1") (class "Default")
      (node (ref "U10") (pin "24") (pinfunction "XD1_24") (pintype "passive"))
      (node (ref "U11") (pin "4") (pinfunction "SD1_4") (pintype "passive"))
      (node (ref "U17") (pin "22") (pinfunction "I/O1_22") (pintype "passive"))
      (node (ref "UD1") (pin "12") (pinfunction "B6_12") (pintype "bidirectional"))
    )
    (net (code "205") (name "/SD2") (class "Default")
      (node (ref "U10") (pin "23") (pinfunction "XD2_23") (pintype "passive"))
      (node (ref "U11") (pin "2") (pinfunction "SD2_2") (pintype "passive"))
      (node (ref "U17") (pin "23") (pinfunction "I/O2_23") (pintype "passive"))
      (node (ref "UD1") (pin "13") (pinfunction "B5_13") (pintype "bidirectional"))
    )
    (net (code "206") (name "/SD3") (class "Default")
      (node (ref "U10") (pin "22") (pinfunction "XD3_22") (pintype "passive"))
      (node (ref "U11") (pin "1") (pinfunction "SD3_1") (pintype "passive"))
      (node (ref "U17") (pin "25") (pinfunction "I/O3_25") (pintype "passive"))
      (node (ref "UD1") (pin "14") (pinfunction "B4_14") (pintype "bidirectional"))
    )
    (net (code "207") (name "/SD4") (class "Default")
      (node (ref "U10") (pin "21") (pinfunction "XD4_21") (pintype "passive"))
      (node (ref "U11") (pin "208") (pinfunction "SD4_208") (pintype "passive"))
      (node (ref "U17") (pin "26") (pinfunction "I/O4_26") (pintype "passive"))
      (node (ref "UD1") (pin "15") (pinfunction "B3_15") (pintype "bidirectional"))
    )
    (net (code "208") (name "/SD5") (class "Default")
      (node (ref "U10") (pin "20") (pinfunction "XD5_20") (pintype "passive"))
      (node (ref "U11") (pin "204") (pinfunction "SD5_204") (pintype "passive"))
      (node (ref "U17") (pin "27") (pinfunction "I/O5_27") (pintype "passive"))
      (node (ref "UD1") (pin "16") (pinfunction "B2_16") (pintype "bidirectional"))
    )
    (net (code "209") (name "/SD6") (class "Default")
      (node (ref "U10") (pin "19") (pinfunction "XD6_19") (pintype "passive"))
      (node (ref "U11") (pin "203") (pinfunction "SD6_203") (pintype "passive"))
      (node (ref "U17") (pin "28") (pinfunction "I/O6_28") (pintype "passive"))
      (node (ref "UD1") (pin "17") (pinfunction "B1_17") (pintype "bidirectional"))
    )
    (net (code "210") (name "/SD7") (class "Default")
      (node (ref "U10") (pin "18") (pinfunction "XD7_18") (pintype "passive"))
      (node (ref "U11") (pin "202") (pinfunction "SD7_202") (pintype "passive"))
      (node (ref "U17") (pin "29") (pinfunction "I/O7_29") (pintype "passive"))
      (node (ref "UD1") (pin "18") (pinfunction "B0_18") (pintype "bidirectional"))
    )
    (net (code "211") (name "/SPEKER") (class "Default")
      (node (ref "R26") (pin "2") (pinfunction "2_2") (pintype "passive"))
      (node (ref "U11") (pin "194") (pinfunction "SPKER_194") (pintype "passive"))
    )
    (net (code "212") (name "/SPEKER_OUT") (class "Default")
      (node (ref "R25") (pin "2") (pinfunction "2_2") (pintype "passive"))
      (node (ref "b1") (pin "2") (pinfunction "2_2") (pintype "passive"))
    )
    (net (code "213") (name "/TBLED") (class "Default")
      (node (ref "U11") (pin "196") (pinfunction "TB_LED+_196") (pintype "passive"))
    )
    (net (code "214") (name "/TB_SW") (class "Default")
      (node (ref "R27") (pin "2") (pinfunction "2_2") (pintype "passive"))
      (node (ref "U11") (pin "195") (pinfunction "TB_SW_195") (pintype "passive"))
    )
    (net (code "215") (name "/VCC_CPU") (class "Default")
      (node (ref "CN1") (pin "17") (pinfunction "17_17") (pintype "passive"))
      (node (ref "CN1") (pin "18") (pinfunction "18_18") (pintype "passive"))
      (node (ref "CN1") (pin "19") (pinfunction "19_19") (pintype "passive"))
      (node (ref "CV39") (pin "1") (pinfunction "1_1") (pintype "passive"))
      (node (ref "CV43") (pin "1") (pinfunction "1_1") (pintype "passive"))
      (node (ref "I4") (pin "10") (pinfunction "10_10") (pintype "passive"))
      (node (ref "I4") (pin "11") (pinfunction "11_11") (pintype "passive"))
      (node (ref "I4") (pin "9") (pinfunction "9_9") (pintype "passive"))
    )
    (net (code "216") (name "GND") (class "Default")
      (node (ref "C1") (pin "2") (pinfunction "2_2") (pintype "passive"))
      (node (ref "C3") (pin "2") (pinfunction "2_2") (pintype "passive"))
      (node (ref "C5") (pin "1") (pinfunction "1_1") (pintype "passive"))
      (node (ref "C8") (pin "2") (pinfunction "2_2") (pintype "passive"))
      (node (ref "C9") (pin "2") (pinfunction "2_2") (pintype "passive"))
      (node (ref "CN1") (pin "22") (pinfunction "22_22") (pintype "passive"))
      (node (ref "CN1") (pin "23") (pinfunction "23_23") (pintype "passive"))
      (node (ref "CN1") (pin "24") (pinfunction "24_24") (pintype "passive"))
      (node (ref "CV1") (pin "2") (pinfunction "2_2") (pintype "passive"))
      (node (ref "CV10") (pin "2") (pinfunction "2_2") (pintype "passive"))
      (node (ref "CV12") (pin "2") (pinfunction "2_2") (pintype "passive"))
      (node (ref "CV13") (pin "2") (pinfunction "2_2") (pintype "passive"))
      (node (ref "CV14") (pin "2") (pinfunction "2_2") (pintype "passive"))
      (node (ref "CV15") (pin "2") (pinfunction "2_2") (pintype "passive"))
      (node (ref "CV16") (pin "2") (pinfunction "2_2") (pintype "passive"))
      (node (ref "CV18") (pin "2") (pinfunction "2_2") (pintype "passive"))
      (node (ref "CV19") (pin "2") (pinfunction "2_2") (pintype "passive"))
      (node (ref "CV2") (pin "2") (pinfunction "2_2") (pintype "passive"))
      (node (ref "CV20") (pin "2") (pinfunction "2_2") (pintype "passive"))
      (node (ref "CV21") (pin "2") (pinfunction "2_2") (pintype "passive"))
      (node (ref "CV22") (pin "2") (pinfunction "2_2") (pintype "passive"))
      (node (ref "CV23") (pin "2") (pinfunction "2_2") (pintype "passive"))
      (node (ref "CV24") (pin "2") (pinfunction "2_2") (pintype "passive"))
      (node (ref "CV25") (pin "2") (pinfunction "2_2") (pintype "passive"))
      (node (ref "CV27") (pin "2") (pinfunction "2_2") (pintype "passive"))
      (node (ref "CV28") (pin "2") (pinfunction "2_2") (pintype "passive"))
      (node (ref "CV29") (pin "2") (pinfunction "2_2") (pintype "passive"))
      (node (ref "CV3") (pin "2") (pinfunction "2_2") (pintype "passive"))
      (node (ref "CV30") (pin "2") (pinfunction "2_2") (pintype "passive"))
      (node (ref "CV31") (pin "2") (pinfunction "2_2") (pintype "passive"))
      (node (ref "CV32") (pin "2") (pinfunction "2_2") (pintype "passive"))
      (node (ref "CV33") (pin "2") (pinfunction "2_2") (pintype "passive"))
      (node (ref "CV35") (pin "2") (pinfunction "2_2") (pintype "passive"))
      (node (ref "CV36") (pin "2") (pinfunction "2_2") (pintype "passive"))
      (node (ref "CV39") (pin "2") (pinfunction "2_2") (pintype "passive"))
      (node (ref "CV4") (pin "2") (pinfunction "2_2") (pintype "passive"))
      (node (ref "CV40") (pin "2") (pinfunction "2_2") (pintype "passive"))
      (node (ref "CV42") (pin "2") (pinfunction "2_2") (pintype "passive"))
      (node (ref "CV43") (pin "2") (pinfunction "2_2") (pintype "passive"))
      (node (ref "CV44") (pin "2") (pinfunction "2_2") (pintype "passive"))
      (node (ref "CV49") (pin "2") (pinfunction "2_2") (pintype "passive"))
      (node (ref "CV50") (pin "2") (pinfunction "2_2") (pintype "passive"))
      (node (ref "CV6") (pin "2") (pinfunction "2_2") (pintype "passive"))
      (node (ref "CV8") (pin "2") (pinfunction "2_2") (pintype "passive"))
      (node (ref "CV9") (pin "2") (pinfunction "2_2") (pintype "passive"))
      (node (ref "I1") (pin "0") (pinfunction "0_0") (pintype "passive"))
      (node (ref "I1") (pin "20") (pinfunction "20_20") (pintype "passive"))
      (node (ref "I1") (pin "32") (pinfunction "32_32") (pintype "passive"))
      (node (ref "I1") (pin "5") (pinfunction "5_5") (pintype "passive"))
      (node (ref "I2") (pin "0") (pinfunction "0_0") (pintype "passive"))
      (node (ref "I2") (pin "16") (pinfunction "16_16") (pintype "passive"))
      (node (ref "I2") (pin "24") (pinfunction "24_24") (pintype "passive"))
      (node (ref "I2") (pin "28") (pinfunction "28_28") (pintype "passive"))
      (node (ref "I2") (pin "36") (pinfunction "36_36") (pintype "passive"))
      (node (ref "I2") (pin "39") (pinfunction "39_39") (pintype "passive"))
      (node (ref "I3") (pin "0") (pinfunction "0_0") (pintype "passive"))
      (node (ref "I3") (pin "11") (pinfunction "11_11") (pintype "passive"))
      (node (ref "I3") (pin "13") (pinfunction "13_13") (pintype "passive"))
      (node (ref "I3") (pin "14") (pinfunction "14_14") (pintype "passive"))
      (node (ref "I3") (pin "21") (pinfunction "21_21") (pintype "passive"))
      (node (ref "I3") (pin "22") (pinfunction "22_22") (pintype "passive"))
      (node (ref "I3") (pin "23") (pinfunction "23_23") (pintype "passive"))
      (node (ref "I3") (pin "30") (pinfunction "30_30") (pintype "passive"))
      (node (ref "I3") (pin "31") (pinfunction "31_31") (pintype "passive"))
      (node (ref "I3") (pin "32") (pinfunction "32_32") (pintype "passive"))
      (node (ref "I3") (pin "39") (pinfunction "39_39") (pintype "passive"))
      (node (ref "I3") (pin "40") (pinfunction "40_40") (pintype "passive"))
      (node (ref "I4") (pin "1") (pinfunction "1_1") (pintype "passive"))
      (node (ref "I4") (pin "2") (pinfunction "2_2") (pintype "passive"))
      (node (ref "I4") (pin "3") (pinfunction "3_3") (pintype "passive"))
      (node (ref "I4") (pin "4") (pinfunction "4_4") (pintype "passive"))
      (node (ref "I4") (pin "5") (pinfunction "5_5") (pintype "passive"))
      (node (ref "I4") (pin "6") (pinfunction "6_6") (pintype "passive"))
      (node (ref "I4") (pin "7") (pinfunction "7_7") (pintype "passive"))
      (node (ref "I4") (pin "8") (pinfunction "8_8") (pintype "passive"))
      (node (ref "LED1") (pin "2") (pintype "passive"))
      (node (ref "M1") (pin "1") (pinfunction "1_1") (pintype "passive"))
      (node (ref "M2") (pin "1") (pinfunction "1_1") (pintype "passive"))
      (node (ref "M3") (pin "1") (pinfunction "1_1") (pintype "passive"))
      (node (ref "M4") (pin "1") (pinfunction "1_1") (pintype "passive"))
      (node (ref "Q1") (pin "E") (pinfunction "e_E") (pintype "passive"))
      (node (ref "Q4") (pin "E") (pinfunction "e_E") (pintype "passive"))
      (node (ref "R11") (pin "1") (pinfunction "1_1") (pintype "passive"))
      (node (ref "R22") (pin "1") (pinfunction "1_1") (pintype "passive"))
      (node (ref "U10") (pin "3") (pinfunction "GND_3") (pintype "passive"))
      (node (ref "U10") (pin "52") (pinfunction "GND_52") (pintype "passive"))
      (node (ref "U10") (pin "77") (pinfunction "GND_77") (pintype "passive"))
      (node (ref "U10") (pin "9") (pinfunction "TEST_9") (pintype "passive"))
      (node (ref "U11") (pin "107") (pinfunction "GND_107") (pintype "passive"))
      (node (ref "U11") (pin "119") (pinfunction "GND_119") (pintype "passive"))
      (node (ref "U11") (pin "130") (pinfunction "GND_130") (pintype "passive"))
      (node (ref "U11") (pin "142") (pinfunction "GND_142") (pintype "passive"))
      (node (ref "U11") (pin "15") (pinfunction "GND_15") (pintype "passive"))
      (node (ref "U11") (pin "154") (pinfunction "GND_154") (pintype "passive"))
      (node (ref "U11") (pin "164") (pinfunction "GND_164") (pintype "passive"))
      (node (ref "U11") (pin "176") (pinfunction "GND_176") (pintype "passive"))
      (node (ref "U11") (pin "189") (pinfunction "GND_189") (pintype "passive"))
      (node (ref "U11") (pin "200") (pinfunction "GND_200") (pintype "passive"))
      (node (ref "U11") (pin "26") (pinfunction "GND_26") (pintype "passive"))
      (node (ref "U11") (pin "3") (pinfunction "GND_3") (pintype "passive"))
      (node (ref "U11") (pin "38") (pinfunction "GND_38") (pintype "passive"))
      (node (ref "U11") (pin "50") (pinfunction "GND_50") (pintype "passive"))
      (node (ref "U11") (pin "60") (pinfunction "GND_60") (pintype "passive"))
      (node (ref "U11") (pin "72") (pinfunction "GND_72") (pintype "passive"))
      (node (ref "U11") (pin "85") (pinfunction "GND_85") (pintype "passive"))
      (node (ref "U11") (pin "96") (pinfunction "GND_96") (pintype "passive"))
      (node (ref "U12") (pin "14") (pinfunction "GND_14") (pintype "passive"))
      (node (ref "U12") (pin "21") (pinfunction "GND_21") (pintype "passive"))
      (node (ref "U12") (pin "25") (pinfunction "GND_25") (pintype "passive"))
      (node (ref "U12") (pin "27") (pinfunction "GND_27") (pintype "passive"))
      (node (ref "U12") (pin "32") (pinfunction "GND_32") (pintype "passive"))
      (node (ref "U12") (pin "34") (pinfunction "GND_34") (pintype "passive"))
      (node (ref "U12") (pin "38") (pinfunction "GND_38") (pintype "passive"))
      (node (ref "U12") (pin "42") (pinfunction "GND_42") (pintype "passive"))
      (node (ref "U12") (pin "5") (pinfunction "GND_5") (pintype "passive"))
      (node (ref "U12") (pin "53") (pinfunction "NUMCLK2_53") (pintype "passive"))
      (node (ref "U12") (pin "55") (pinfunction "GND_55") (pintype "passive"))
      (node (ref "U12") (pin "60") (pinfunction "GND_60") (pintype "passive"))
      (node (ref "U12") (pin "61") (pinfunction "GND_61") (pintype "passive"))
      (node (ref "U12") (pin "63") (pinfunction "GND_63") (pintype "passive"))
      (node (ref "U12") (pin "66") (pinfunction "GND_66") (pintype "passive"))
      (node (ref "U16") (pin "7") (pinfunction "GND_7") (pintype "power_in"))
      (node (ref "U17") (pin "24") (pinfunction "GND_24") (pintype "passive"))
      (node (ref "U18") (pin "3") (pinfunction "GND_3") (pintype "passive"))
      (node (ref "U3") (pin "2") (pinfunction "GND_2") (pintype "passive"))
      (node (ref "UD1") (pin "10") (pinfunction "GND_10") (pintype "power_in"))
    )
    (net (code "217") (name "Net-(C31-Pad1)") (class "Default")
      (node (ref "C31") (pin "1") (pinfunction "1_1") (pintype "passive"))
      (node (ref "R24") (pin "1") (pinfunction "1_1") (pintype "passive"))
      (node (ref "U16") (pin "1") (pintype "input"))
    )
    (net (code "218") (name "Net-(C31-Pad2)") (class "Default")
      (node (ref "C31") (pin "2") (pinfunction "2_2") (pintype "passive"))
      (node (ref "X3") (pin "2") (pinfunction "2_2") (pintype "passive"))
    )
    (net (code "219") (name "Net-(D1-PadA)") (class "Default")
      (node (ref "D1") (pin "A") (pinfunction "A_A") (pintype "passive"))
      (node (ref "D2") (pin "A") (pinfunction "A_A") (pintype "passive"))
      (node (ref "R12") (pin "A") (pinfunction "A_A") (pintype "passive"))
      (node (ref "R13") (pin "2") (pinfunction "2_2") (pintype "passive"))
    )
    (net (code "220") (name "Net-(D1-PadK)") (class "Default")
      (node (ref "D1") (pin "K") (pinfunction "K_K") (pintype "passive"))
      (node (ref "U16") (pin "10") (pintype "output"))
    )
    (net (code "221") (name "Net-(D2-PadK)") (class "Default")
      (node (ref "D2") (pin "K") (pinfunction "K_K") (pintype "passive"))
      (node (ref "U16") (pin "12") (pintype "output"))
    )
    (net (code "222") (name "Net-(LED1-Pad1)") (class "Default")
      (node (ref "LED1") (pin "1") (pintype "passive"))
      (node (ref "RL1") (pin "1") (pinfunction "1_1") (pintype "passive"))
    )
    (net (code "223") (name "Net-(Q1-b)") (class "Default")
      (node (ref "Q1") (pin "B") (pinfunction "b_B") (pintype "passive"))
      (node (ref "R11") (pin "2") (pinfunction "2_2") (pintype "passive"))
      (node (ref "R12") (pin "K") (pinfunction "K_K") (pintype "passive"))
    )
    (net (code "224") (name "Net-(Q4-b)") (class "Default")
      (node (ref "Q4") (pin "B") (pinfunction "b_B") (pintype "passive"))
      (node (ref "R26") (pin "1") (pinfunction "1_1") (pintype "passive"))
    )
    (net (code "225") (name "Net-(Q4-c)") (class "Default")
      (node (ref "Q4") (pin "C") (pinfunction "c_C") (pintype "passive"))
      (node (ref "R25") (pin "1") (pinfunction "1_1") (pintype "passive"))
    )
    (net (code "226") (name "Net-(R24-Pad2)") (class "Default")
      (node (ref "R24") (pin "2") (pinfunction "2_2") (pintype "passive"))
      (node (ref "U16") (pin "2") (pintype "output"))
      (node (ref "U16") (pin "3") (pintype "input"))
    )
    (net (code "227") (name "Net-(U3-XI)") (class "Default")
      (node (ref "U3") (pin "4") (pinfunction "XI_4") (pintype "passive"))
      (node (ref "X4") (pin "2") (pinfunction "2_2") (pintype "passive"))
    )
    (net (code "228") (name "Net-(U3-XO{slash}FIN)") (class "Default")
      (node (ref "U3") (pin "3") (pinfunction "XO/FIN_3") (pintype "passive"))
      (node (ref "X4") (pin "1") (pinfunction "1_1") (pintype "passive"))
    )
    (net (code "229") (name "Net-(U16-Pad4)") (class "Default")
      (node (ref "U16") (pin "4") (pintype "output"))
      (node (ref "U16") (pin "5") (pintype "input"))
      (node (ref "X3") (pin "1") (pinfunction "1_1") (pintype "passive"))
    )
    (net (code "230") (name "VCC") (class "Default")
      (node (ref "CV1") (pin "1") (pinfunction "1_1") (pintype "passive"))
      (node (ref "CV12") (pin "1") (pinfunction "1_1") (pintype "passive"))
      (node (ref "CV13") (pin "1") (pinfunction "1_1") (pintype "passive"))
      (node (ref "CV14") (pin "1") (pinfunction "1_1") (pintype "passive"))
      (node (ref "CV15") (pin "1") (pinfunction "1_1") (pintype "passive"))
      (node (ref "CV16") (pin "1") (pinfunction "1_1") (pintype "passive"))
      (node (ref "CV18") (pin "1") (pinfunction "1_1") (pintype "passive"))
      (node (ref "CV19") (pin "1") (pinfunction "1_1") (pintype "passive"))
      (node (ref "CV2") (pin "1") (pinfunction "1_1") (pintype "passive"))
      (node (ref "CV20") (pin "1") (pinfunction "1_1") (pintype "passive"))
      (node (ref "CV21") (pin "1") (pinfunction "1_1") (pintype "passive"))
      (node (ref "CV22") (pin "1") (pinfunction "1_1") (pintype "passive"))
      (node (ref "CV23") (pin "1") (pinfunction "1_1") (pintype "passive"))
      (node (ref "CV24") (pin "1") (pinfunction "1_1") (pintype "passive"))
      (node (ref "CV25") (pin "1") (pinfunction "1_1") (pintype "passive"))
      (node (ref "CV27") (pin "1") (pinfunction "1_1") (pintype "passive"))
      (node (ref "CV28") (pin "1") (pinfunction "1_1") (pintype "passive"))
      (node (ref "CV29") (pin "1") (pinfunction "1_1") (pintype "passive"))
      (node (ref "CV3") (pin "1") (pinfunction "1_1") (pintype "passive"))
      (node (ref "CV30") (pin "1") (pinfunction "1_1") (pintype "passive"))
      (node (ref "CV31") (pin "1") (pinfunction "1_1") (pintype "passive"))
      (node (ref "CV32") (pin "1") (pinfunction "1_1") (pintype "passive"))
      (node (ref "CV33") (pin "1") (pinfunction "1_1") (pintype "passive"))
      (node (ref "CV35") (pin "1") (pinfunction "1_1") (pintype "passive"))
      (node (ref "CV36") (pin "1") (pinfunction "1_1") (pintype "passive"))
      (node (ref "CV4") (pin "1") (pinfunction "1_1") (pintype "passive"))
      (node (ref "CV40") (pin "1") (pinfunction "1_1") (pintype "passive"))
      (node (ref "CV42") (pin "1") (pinfunction "1_1") (pintype "passive"))
      (node (ref "CV44") (pin "1") (pinfunction "1_1") (pintype "passive"))
      (node (ref "CV49") (pin "1") (pinfunction "1_1") (pintype "passive"))
      (node (ref "CV50") (pin "1") (pinfunction "1_1") (pintype "passive"))
      (node (ref "CV6") (pin "1") (pinfunction "1_1") (pintype "passive"))
      (node (ref "CV8") (pin "1") (pinfunction "1_1") (pintype "passive"))
      (node (ref "D3") (pin "A") (pinfunction "A_A") (pintype "passive"))
      (node (ref "I3") (pin "16") (pinfunction "16_16") (pintype "passive"))
      (node (ref "I3") (pin "17") (pinfunction "17_17") (pintype "passive"))
      (node (ref "I3") (pin "25") (pinfunction "25_25") (pintype "passive"))
      (node (ref "I3") (pin "26") (pinfunction "26_26") (pintype "passive"))
      (node (ref "I3") (pin "36") (pinfunction "36_36") (pintype "passive"))
      (node (ref "I3") (pin "37") (pinfunction "37_37") (pintype "passive"))
      (node (ref "I4") (pin "12") (pinfunction "12_12") (pintype "passive"))
      (node (ref "I4") (pin "13") (pinfunction "13_13") (pintype "passive"))
      (node (ref "I4") (pin "14") (pinfunction "14_14") (pintype "passive"))
      (node (ref "I4") (pin "15") (pinfunction "15_15") (pintype "passive"))
      (node (ref "R1") (pin "2") (pinfunction "2_2") (pintype "passive"))
      (node (ref "R13") (pin "1") (pinfunction "1_1") (pintype "passive"))
      (node (ref "R14") (pin "1") (pinfunction "1_1") (pintype "passive"))
      (node (ref "R15") (pin "1") (pinfunction "1_1") (pintype "passive"))
      (node (ref "R16") (pin "1") (pinfunction "1_1") (pintype "passive"))
      (node (ref "R17") (pin "1") (pinfunction "1_1") (pintype "passive"))
      (node (ref "R19") (pin "1") (pinfunction "1_1") (pintype "passive"))
      (node (ref "R27") (pin "1") (pinfunction "1_1") (pintype "passive"))
      (node (ref "R28") (pin "1") (pinfunction "1_1") (pintype "passive"))
      (node (ref "R29") (pin "1") (pinfunction "1_1") (pintype "passive"))
      (node (ref "R30") (pin "1") (pinfunction "1_1") (pintype "passive"))
      (node (ref "R31") (pin "1") (pinfunction "1_1") (pintype "passive"))
      (node (ref "R32") (pin "1") (pinfunction "1_1") (pintype "passive"))
      (node (ref "R33") (pin "1") (pinfunction "1_1") (pintype "passive"))
      (node (ref "R34") (pin "1") (pinfunction "1_1") (pintype "passive"))
      (node (ref "R35") (pin "1") (pinfunction "1_1") (pintype "passive"))
      (node (ref "R36") (pin "1") (pinfunction "1_1") (pintype "passive"))
      (node (ref "R37") (pin "1") (pinfunction "1_1") (pintype "passive"))
      (node (ref "R38") (pin "1") (pinfunction "1_1") (pintype "passive"))
      (node (ref "R39") (pin "1") (pinfunction "1_1") (pintype "passive"))
      (node (ref "R40") (pin "1") (pinfunction "1_1") (pintype "passive"))
      (node (ref "R41") (pin "1") (pinfunction "1_1") (pintype "passive"))
      (node (ref "R42") (pin "1") (pinfunction "1_1") (pintype "passive"))
      (node (ref "R43") (pin "1") (pinfunction "1_1") (pintype "passive"))
      (node (ref "R44") (pin "1") (pinfunction "1_1") (pintype "passive"))
      (node (ref "R45") (pin "1") (pinfunction "1_1") (pintype "passive"))
      (node (ref "R46") (pin "1") (pinfunction "1_1") (pintype "passive"))
      (node (ref "R47") (pin "1") (pinfunction "1_1") (pintype "passive"))
      (node (ref "R5") (pin "2") (pinfunction "2_2") (pintype "passive"))
      (node (ref "RL1") (pin "2") (pinfunction "2_2") (pintype "passive"))
      (node (ref "RN2_4") (pin "2") (pinfunction "2_2") (pintype "passive"))
      (node (ref "RR") (pin "2") (pinfunction "2_2") (pintype "passive"))
      (node (ref "U11") (pin "10") (pinfunction "VCC_10") (pintype "passive"))
      (node (ref "U11") (pin "100") (pinfunction "VCC_100") (pintype "passive"))
      (node (ref "U11") (pin "114") (pinfunction "VCC_114") (pintype "passive"))
      (node (ref "U11") (pin "131") (pinfunction "VCC_131") (pintype "passive"))
      (node (ref "U11") (pin "147") (pinfunction "VCC_147") (pintype "passive"))
      (node (ref "U11") (pin "165") (pinfunction "VCC_165") (pintype "passive"))
      (node (ref "U11") (pin "183") (pinfunction "VCC_183") (pintype "passive"))
      (node (ref "U11") (pin "201") (pinfunction "VCC_201") (pintype "passive"))
      (node (ref "U11") (pin "27") (pinfunction "VCC_27") (pintype "passive"))
      (node (ref "U11") (pin "43") (pinfunction "VCC_43") (pintype "passive"))
      (node (ref "U11") (pin "61") (pinfunction "VCC_61") (pintype "passive"))
      (node (ref "U11") (pin "79") (pinfunction "VCC_79") (pintype "passive"))
      (node (ref "U11") (pin "97") (pinfunction "VCC_97") (pintype "passive"))
      (node (ref "U12") (pin "13") (pinfunction "VCC_13") (pintype "passive"))
      (node (ref "U12") (pin "22") (pinfunction "VCC_22") (pintype "passive"))
      (node (ref "U12") (pin "26") (pinfunction "VCC_26") (pintype "passive"))
      (node (ref "U12") (pin "31") (pinfunction "VCC_31") (pintype "passive"))
      (node (ref "U12") (pin "33") (pinfunction "VCC_33") (pintype "passive"))
      (node (ref "U12") (pin "37") (pinfunction "VCC_37") (pintype "passive"))
      (node (ref "U12") (pin "39") (pinfunction "VCC_39") (pintype "passive"))
      (node (ref "U12") (pin "4") (pinfunction "VCC_4") (pintype "passive"))
      (node (ref "U12") (pin "40") (pinfunction "STEN_40") (pintype "passive"))
      (node (ref "U12") (pin "43") (pinfunction "VCC_43") (pintype "passive"))
      (node (ref "U12") (pin "46") (pinfunction "VCC_46") (pintype "passive"))
      (node (ref "U12") (pin "50") (pinfunction "VCC_50") (pintype "passive"))
      (node (ref "U12") (pin "58") (pinfunction "VCC_58") (pintype "passive"))
      (node (ref "U12") (pin "59") (pinfunction "CKM_59") (pintype "passive"))
      (node (ref "U12") (pin "62") (pinfunction "VCC_62") (pintype "passive"))
      (node (ref "U12") (pin "64") (pinfunction "VCC_64") (pintype "passive"))
      (node (ref "U12") (pin "9") (pinfunction "VCC_9") (pintype "passive"))
      (node (ref "U16") (pin "14") (pinfunction "VCC_14") (pintype "power_in"))
      (node (ref "U17") (pin "7") (pinfunction "~{WE}_7") (pintype "passive"))
      (node (ref "U17") (pin "8") (pinfunction "VCC_8") (pintype "passive"))
      (node (ref "U18") (pin "5") (pinfunction "VCC_5") (pintype "passive"))
      (node (ref "U3") (pin "7") (pinfunction "VCC_7") (pintype "passive"))
      (node (ref "UD1") (pin "20") (pinfunction "VCC_20") (pintype "power_in"))
      (node (ref "b1") (pin "1") (pinfunction "1_1") (pintype "passive"))
    )
    (net (code "231") (name "unconnected-(CN1-Pad0)") (class "Default")
      (node (ref "CN1") (pin "0") (pinfunction "0_0") (pintype "passive"))
    )
    (net (code "232") (name "unconnected-(I2-Pad40)") (class "Default")
      (node (ref "I2") (pin "40") (pinfunction "40_40") (pintype "passive"))
    )
    (net (code "233") (name "unconnected-(I2-Pad42)") (class "Default")
      (node (ref "I2") (pin "42") (pinfunction "42_42") (pintype "passive"))
    )
    (net (code "234") (name "unconnected-(I2-Pad44)") (class "Default")
      (node (ref "I2") (pin "44") (pinfunction "44_44") (pintype "passive"))
    )
    (net (code "235") (name "unconnected-(U10-NC-Pad2)") (class "Default")
      (node (ref "U10") (pin "2") (pinfunction "NC_2") (pintype "passive"))
    )
    (net (code "236") (name "unconnected-(U10-NC-Pad4)") (class "Default")
      (node (ref "U10") (pin "4") (pinfunction "NC_4") (pintype "passive"))
    )
    (net (code "237") (name "unconnected-(U10-NC-Pad11)") (class "Default")
      (node (ref "U10") (pin "11") (pinfunction "NC_11") (pintype "passive"))
    )
    (net (code "238") (name "unconnected-(U10-NC-Pad12)") (class "Default")
      (node (ref "U10") (pin "12") (pinfunction "NC_12") (pintype "passive"))
    )
    (net (code "239") (name "unconnected-(U10-NC-Pad27)") (class "Default")
      (node (ref "U10") (pin "27") (pinfunction "NC_27") (pintype "passive"))
    )
    (net (code "240") (name "unconnected-(U10-NC-Pad28)") (class "Default")
      (node (ref "U10") (pin "28") (pinfunction "NC_28") (pintype "passive"))
    )
    (net (code "241") (name "unconnected-(U10-NC-Pad29)") (class "Default")
      (node (ref "U10") (pin "29") (pinfunction "NC_29") (pintype "passive"))
    )
    (net (code "242") (name "unconnected-(U10-NC-Pad40)") (class "Default")
      (node (ref "U10") (pin "40") (pinfunction "NC_40") (pintype "passive"))
    )
    (net (code "243") (name "unconnected-(U10-NC-Pad51)") (class "Default")
      (node (ref "U10") (pin "51") (pinfunction "NC_51") (pintype "passive"))
    )
    (net (code "244") (name "unconnected-(U10-NC-Pad53)") (class "Default")
      (node (ref "U10") (pin "53") (pinfunction "NC_53") (pintype "passive"))
    )
    (net (code "245") (name "unconnected-(U10-NC-Pad66)") (class "Default")
      (node (ref "U10") (pin "66") (pinfunction "NC_66") (pintype "passive"))
    )
    (net (code "246") (name "unconnected-(U10-NC-Pad67)") (class "Default")
      (node (ref "U10") (pin "67") (pinfunction "NC_67") (pintype "passive"))
    )
    (net (code "247") (name "unconnected-(U10-NC-Pad68)") (class "Default")
      (node (ref "U10") (pin "68") (pinfunction "NC_68") (pintype "passive"))
    )
    (net (code "248") (name "unconnected-(U10-NC-Pad88)") (class "Default")
      (node (ref "U10") (pin "88") (pinfunction "NC_88") (pintype "passive"))
    )
    (net (code "249") (name "unconnected-(U10-NC-Pad89)") (class "Default")
      (node (ref "U10") (pin "89") (pinfunction "NC_89") (pintype "passive"))
    )
    (net (code "250") (name "unconnected-(U10-NC-Pad90)") (class "Default")
      (node (ref "U10") (pin "90") (pinfunction "NC_90") (pintype "passive"))
    )
    (net (code "251") (name "unconnected-(U11-A245-DIR(NC)-Pad21)") (class "Default")
      (node (ref "U11") (pin "21") (pinfunction "A245-DIR(NC)_21") (pintype "passive"))
    )
    (net (code "252") (name "unconnected-(U11-NC-Pad52)") (class "Default")
      (node (ref "U11") (pin "52") (pinfunction "NC_52") (pintype "passive"))
    )
    (net (code "253") (name "unconnected-(U11-NC-Pad53)") (class "Default")
      (node (ref "U11") (pin "53") (pinfunction "NC_53") (pintype "passive"))
    )
    (net (code "254") (name "unconnected-(U11-NC-Pad54)") (class "Default")
      (node (ref "U11") (pin "54") (pinfunction "NC_54") (pintype "passive"))
    )
    (net (code "255") (name "unconnected-(U11-NC-Pad128)") (class "Default")
      (node (ref "U11") (pin "128") (pinfunction "NC_128") (pintype "passive"))
    )
    (net (code "256") (name "unconnected-(U11-NC-Pad129)") (class "Default")
      (node (ref "U11") (pin "129") (pinfunction "NC_129") (pintype "passive"))
    )
    (net (code "257") (name "unconnected-(U12-NC-Pad1)") (class "Default")
      (node (ref "U12") (pin "1") (pinfunction "NC_1") (pintype "passive"))
    )
    (net (code "258") (name "unconnected-(U12-NC-Pad10)") (class "Default")
      (node (ref "U12") (pin "10") (pinfunction "NC_10") (pintype "passive"))
    )
    (net (code "259") (name "unconnected-(U12-NC-Pad17)") (class "Default")
      (node (ref "U12") (pin "17") (pinfunction "NC_17") (pintype "passive"))
    )
    (net (code "260") (name "unconnected-(U12-NC-Pad18)") (class "Default")
      (node (ref "U12") (pin "18") (pinfunction "NC_18") (pintype "passive"))
    )
    (net (code "261") (name "unconnected-(U12-NC-Pad52)") (class "Default")
      (node (ref "U12") (pin "52") (pinfunction "NC_52") (pintype "passive"))
    )
    (net (code "262") (name "unconnected-(U12-NC-Pad65)") (class "Default")
      (node (ref "U12") (pin "65") (pinfunction "NC_65") (pintype "passive"))
    )
    (net (code "263") (name "unconnected-(U12-NC-Pad67)") (class "Default")
      (node (ref "U12") (pin "67") (pinfunction "NC_67") (pintype "passive"))
    )
    (net (code "264") (name "unconnected-(U12-NC-Pad68)") (class "Default")
      (node (ref "U12") (pin "68") (pinfunction "NC_68") (pintype "passive"))
    )
    (net (code "265") (name "unconnected-(U12-~{READY0}-Pad57)") (class "Default")
      (node (ref "U12") (pin "57") (pinfunction "~{READY0}_57") (pintype "passive"))
    )
    (net (code "266") (name "unconnected-(U16-Pad8)") (class "Default")
      (node (ref "U16") (pin "8") (pintype "output"))
    )
    (net (code "267") (name "unconnected-(U16-Pad9)") (class "Default")
      (node (ref "U16") (pin "9") (pintype "input"))
    )
    (net (code "268") (name "unconnected-(U17-NC-Pad6)") (class "Default")
      (node (ref "U17") (pin "6") (pinfunction "NC_6") (pintype "passive"))
    )
    (net (code "269") (name "unconnected-(U17-NC-Pad9)") (class "Default")
      (node (ref "U17") (pin "9") (pinfunction "NC_9") (pintype "passive"))
    )
    (net (code "270") (name "unconnected-(U17-NC-Pad10)") (class "Default")
      (node (ref "U17") (pin "10") (pinfunction "NC_10") (pintype "passive"))
    )
  )
)
